# Clock_EasyEDA_Project_File.net
KiCad netlist of a schematic drawn in EasyEDA Pro
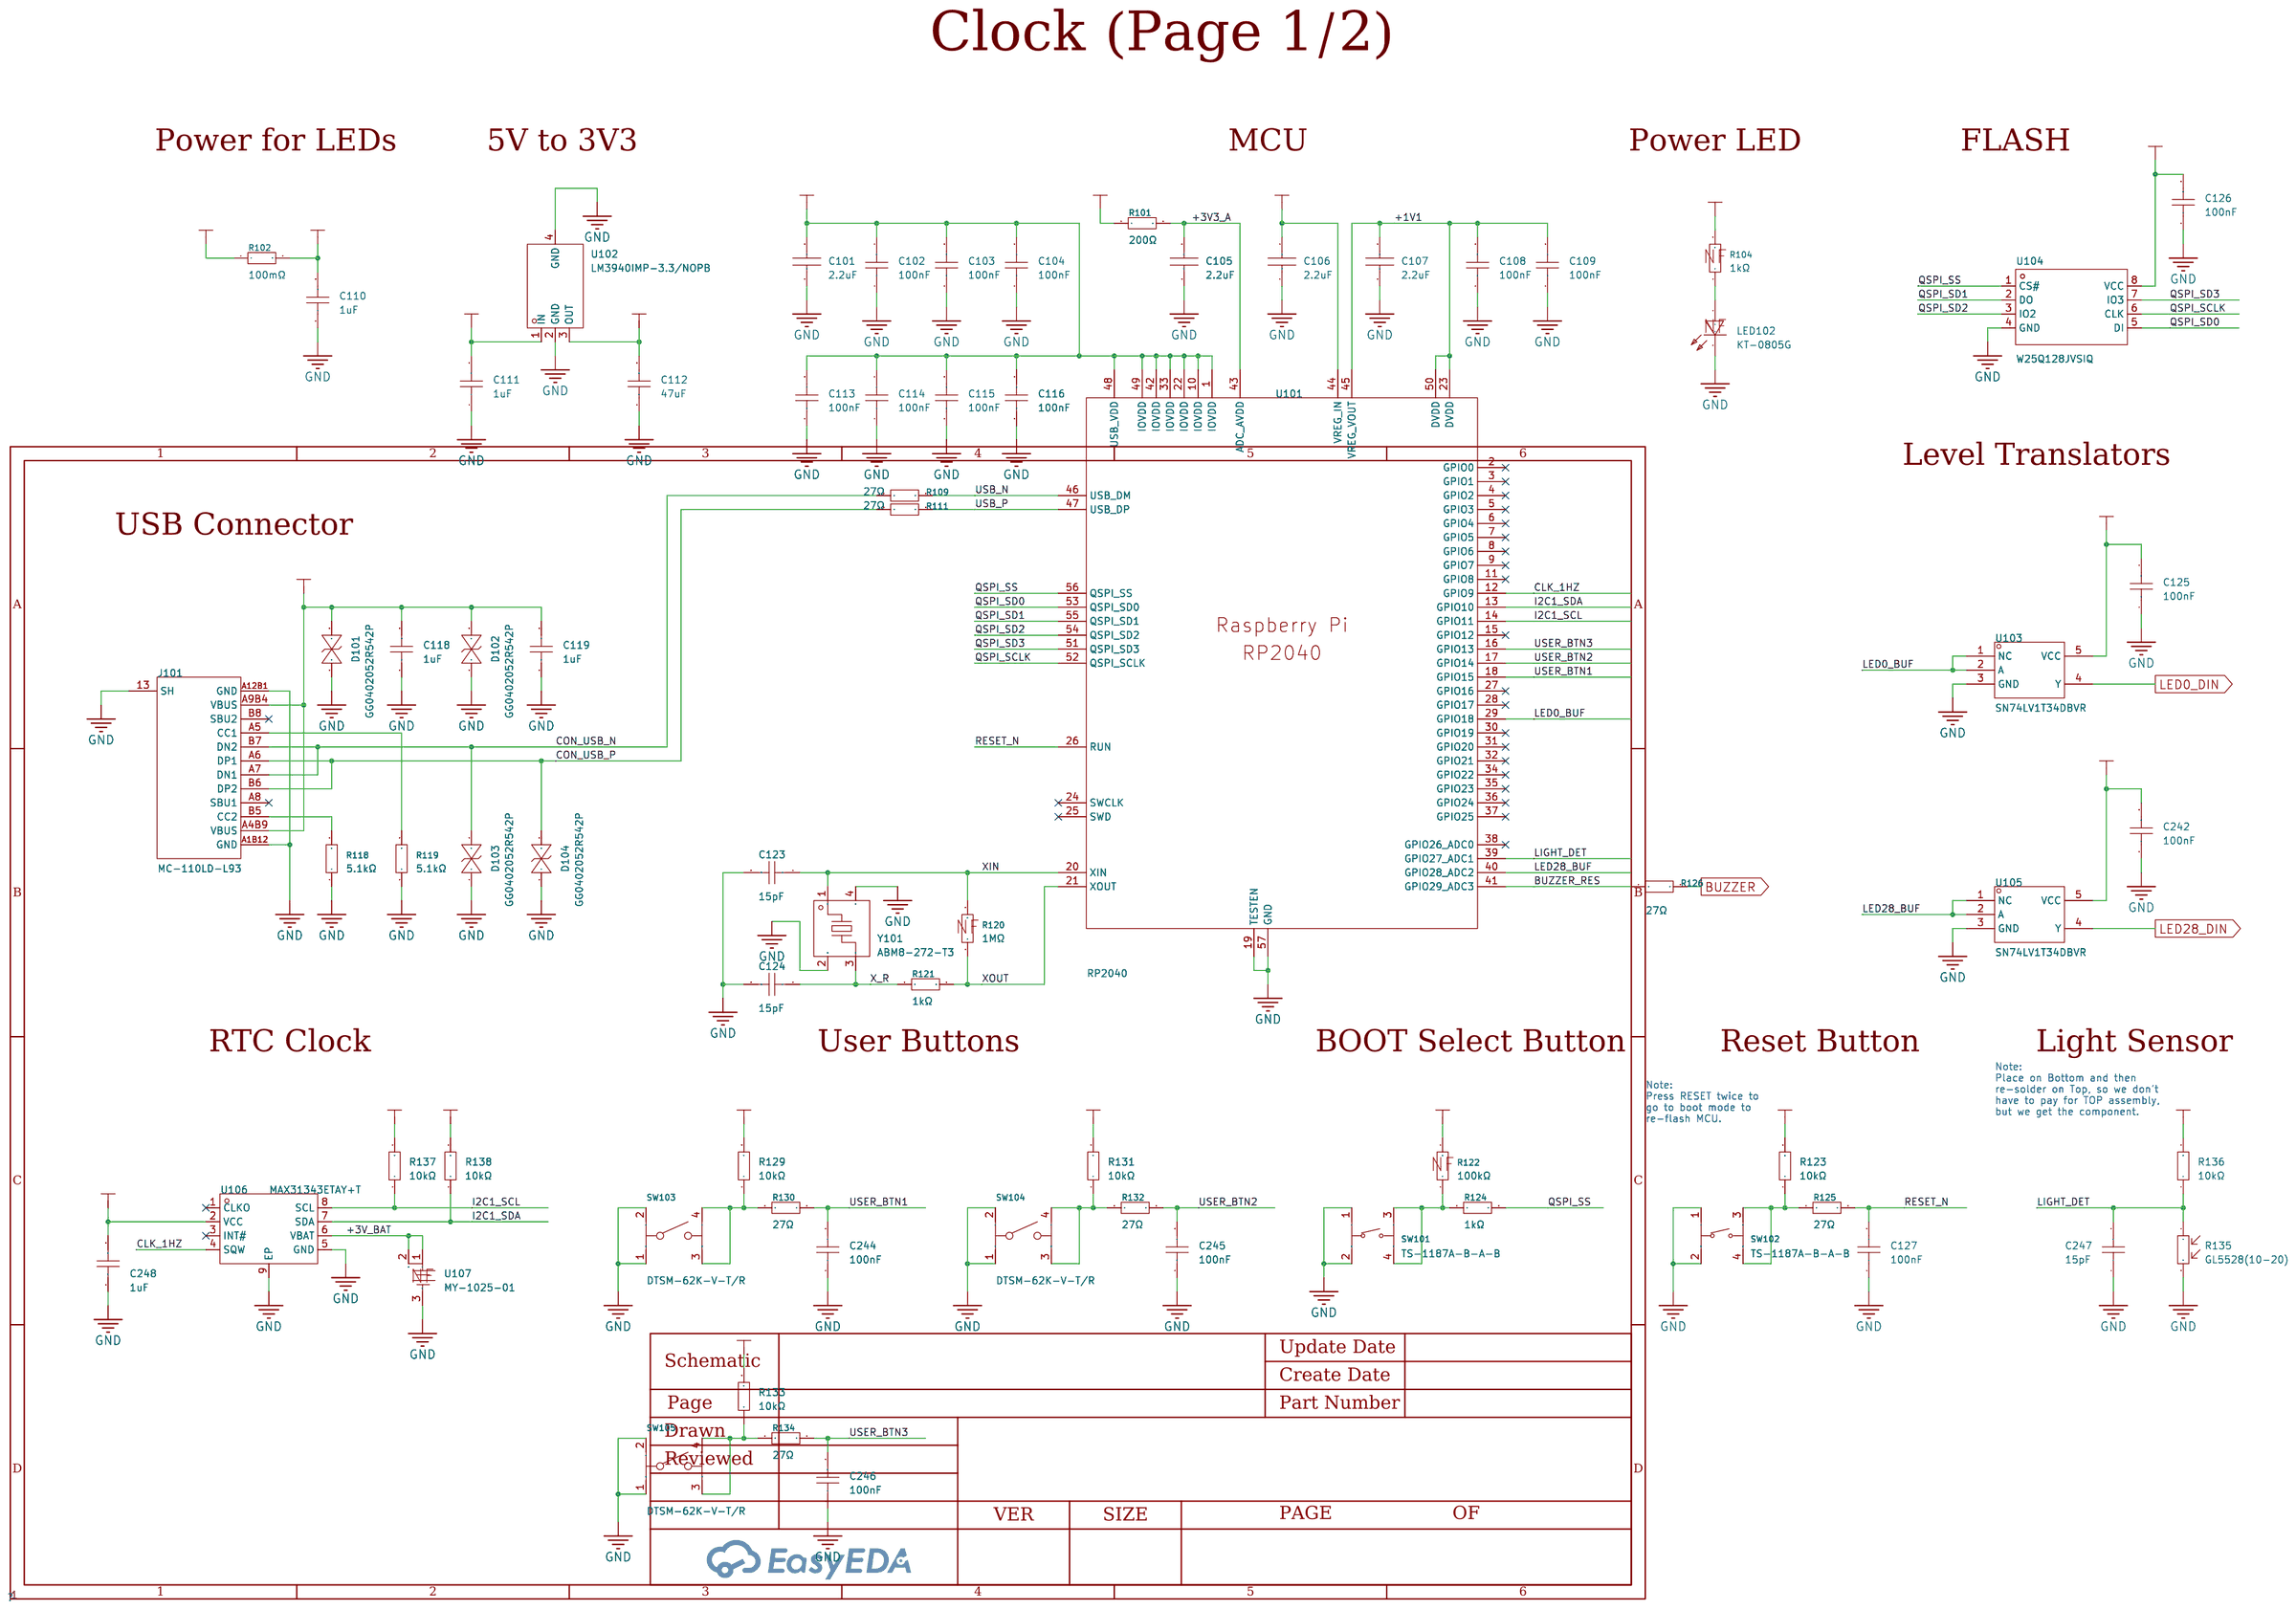
[diagram p0: MCU]
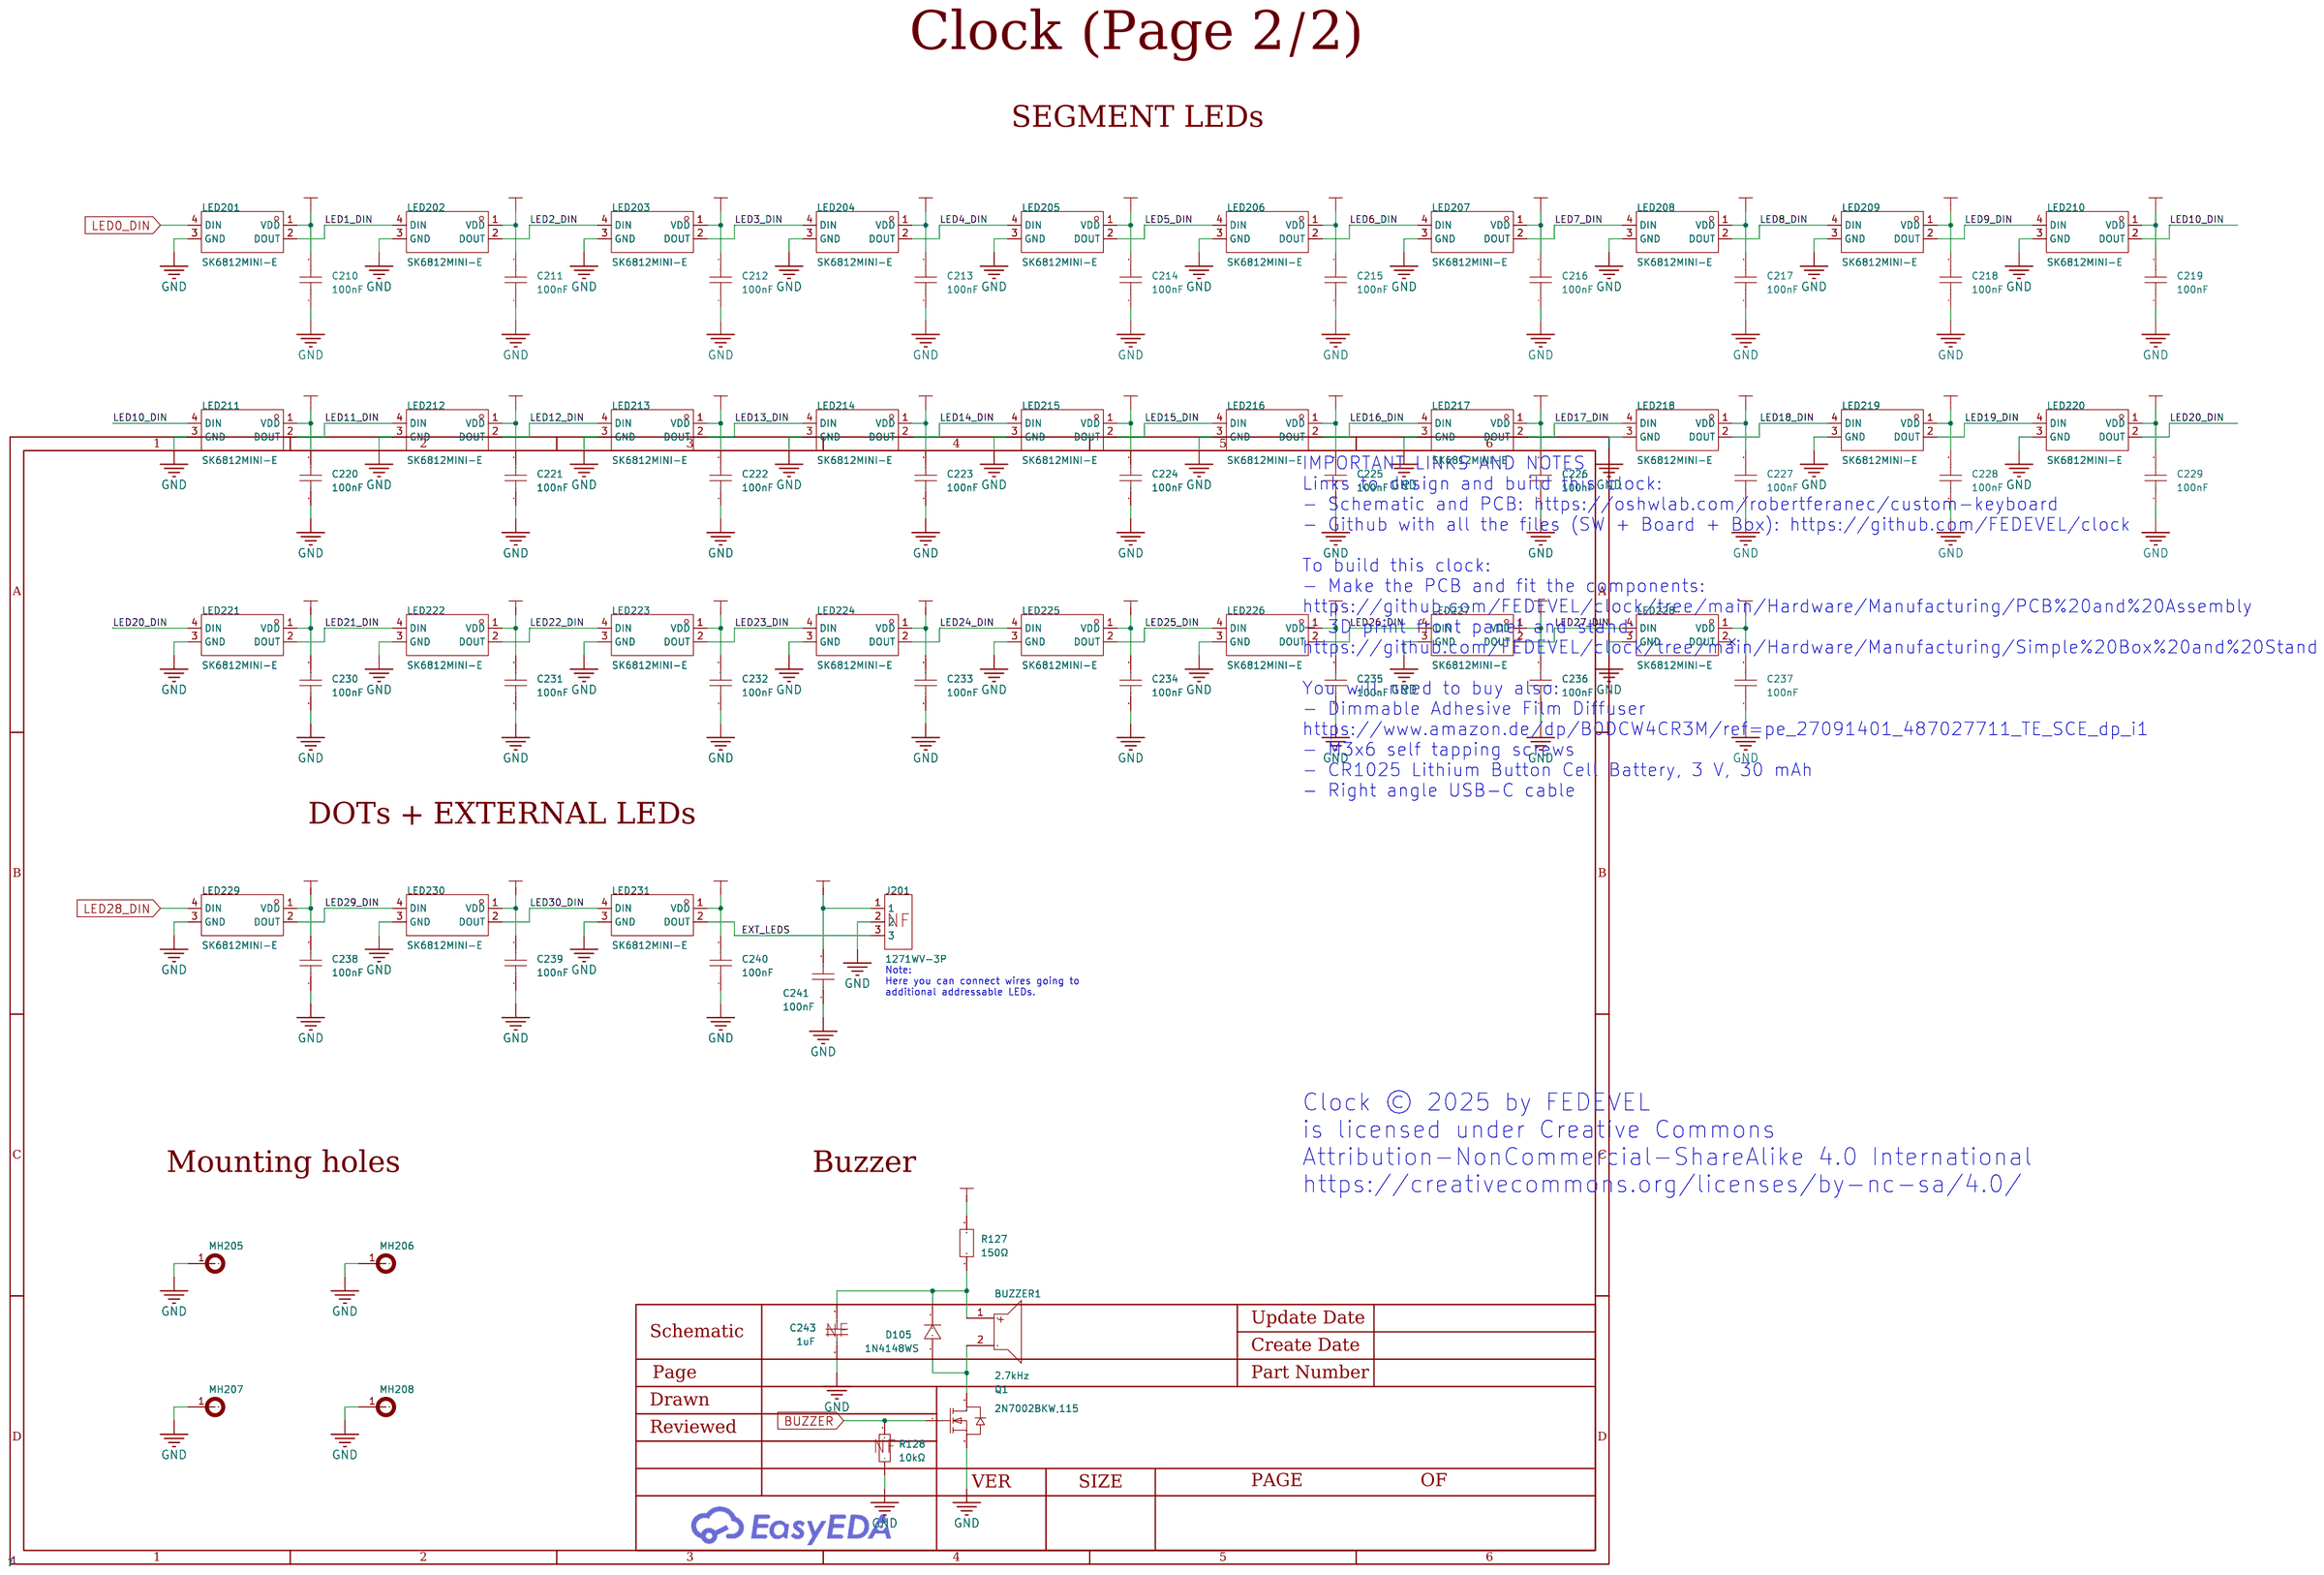
[diagram p1: OTHER]

(export (version "E")
  (design (tool "Eeschema 10.0.6"))
  (components
    (comp (ref "C101")
      (value "2.2uF")
      (footprint "easyedapro:C0402")
      (fields
        (field (name "Manufacturer Part") "CL05A225MQ5NSNC")
        (field (name "Manufacturer") "SAMSUNG(三星)")
      )
      (libsource (lib "easyedapro") (part "CL05A225MQ5NSNC"))
    )
    (comp (ref "C102")
      (value "100nF")
      (footprint "easyedapro:C0402")
      (fields
        (field (name "Manufacturer Part") "CL05B104KO5NNNC")
        (field (name "Manufacturer") "SAMSUNG(三星)")
      )
      (libsource (lib "easyedapro") (part "CL05B104KO5NNNC"))
    )
    (comp (ref "C103")
      (value "100nF")
      (footprint "easyedapro:C0402")
      (fields
        (field (name "Manufacturer Part") "CL05B104KO5NNNC")
        (field (name "Manufacturer") "SAMSUNG(三星)")
      )
      (libsource (lib "easyedapro") (part "CL05B104KO5NNNC"))
    )
    (comp (ref "C104")
      (value "100nF")
      (footprint "easyedapro:C0402")
      (fields
        (field (name "Manufacturer Part") "CL05B104KO5NNNC")
        (field (name "Manufacturer") "SAMSUNG(三星)")
      )
      (libsource (lib "easyedapro") (part "CL05B104KO5NNNC"))
    )
    (comp (ref "C105")
      (value "2.2uF")
      (footprint "easyedapro:C0402")
      (fields
        (field (name "Manufacturer Part") "CL05A225MQ5NSNC")
        (field (name "Manufacturer") "SAMSUNG(三星)")
      )
      (libsource (lib "easyedapro") (part "CL05A225MQ5NSNC"))
    )
    (comp (ref "C106")
      (value "2.2uF")
      (footprint "easyedapro:C0402")
      (fields
        (field (name "Manufacturer Part") "CL05A225MQ5NSNC")
        (field (name "Manufacturer") "SAMSUNG(三星)")
      )
      (libsource (lib "easyedapro") (part "CL05A225MQ5NSNC"))
    )
    (comp (ref "C107")
      (value "2.2uF")
      (footprint "easyedapro:C0402")
      (fields
        (field (name "Manufacturer Part") "CL05A225MQ5NSNC")
        (field (name "Manufacturer") "SAMSUNG(三星)")
      )
      (libsource (lib "easyedapro") (part "CL05A225MQ5NSNC"))
    )
    (comp (ref "C108")
      (value "100nF")
      (footprint "easyedapro:C0402")
      (fields
        (field (name "Manufacturer Part") "CL05B104KO5NNNC")
        (field (name "Manufacturer") "SAMSUNG(三星)")
      )
      (libsource (lib "easyedapro") (part "CL05B104KO5NNNC"))
    )
    (comp (ref "C109")
      (value "100nF")
      (footprint "easyedapro:C0402")
      (fields
        (field (name "Manufacturer Part") "CL05B104KO5NNNC")
        (field (name "Manufacturer") "SAMSUNG(三星)")
      )
      (libsource (lib "easyedapro") (part "CL05B104KO5NNNC"))
    )
    (comp (ref "C110")
      (value "1uF")
      (footprint "easyedapro:C0402")
      (fields
        (field (name "Manufacturer Part") "CL05A105KA5NQNC")
        (field (name "Manufacturer") "SAMSUNG(三星)")
      )
      (libsource (lib "easyedapro") (part "CL05A105KA5NQNC"))
    )
    (comp (ref "C111")
      (value "1uF")
      (footprint "easyedapro:C0402")
      (fields
        (field (name "Manufacturer Part") "CL05A105KA5NQNC")
        (field (name "Manufacturer") "SAMSUNG(三星)")
      )
      (libsource (lib "easyedapro") (part "CL05A105KA5NQNC"))
    )
    (comp (ref "C112")
      (value "47uF")
      (footprint "easyedapro:C1206")
      (fields
        (field (name "Manufacturer Part") "CL31A476MPHNNNE")
        (field (name "Manufacturer") "SAMSUNG(三星)")
      )
      (libsource (lib "easyedapro") (part "CL31A476MPHNNNE"))
    )
    (comp (ref "C113")
      (value "100nF")
      (footprint "easyedapro:C0402")
      (fields
        (field (name "Manufacturer Part") "CL05B104KO5NNNC")
        (field (name "Manufacturer") "SAMSUNG(三星)")
      )
      (libsource (lib "easyedapro") (part "CL05B104KO5NNNC"))
    )
    (comp (ref "C114")
      (value "100nF")
      (footprint "easyedapro:C0402")
      (fields
        (field (name "Manufacturer Part") "CL05B104KO5NNNC")
        (field (name "Manufacturer") "SAMSUNG(三星)")
      )
      (libsource (lib "easyedapro") (part "CL05B104KO5NNNC"))
    )
    (comp (ref "C115")
      (value "100nF")
      (footprint "easyedapro:C0402")
      (fields
        (field (name "Manufacturer Part") "CL05B104KO5NNNC")
        (field (name "Manufacturer") "SAMSUNG(三星)")
      )
      (libsource (lib "easyedapro") (part "CL05B104KO5NNNC"))
    )
    (comp (ref "C116")
      (value "100nF")
      (footprint "easyedapro:C0402")
      (fields
        (field (name "Manufacturer Part") "CL05B104KO5NNNC")
        (field (name "Manufacturer") "SAMSUNG(三星)")
      )
      (libsource (lib "easyedapro") (part "CL05B104KO5NNNC"))
    )
    (comp (ref "C118")
      (value "1uF")
      (footprint "easyedapro:C0402")
      (fields
        (field (name "Manufacturer Part") "CL05A105KA5NQNC")
        (field (name "Manufacturer") "SAMSUNG(三星)")
      )
      (libsource (lib "easyedapro") (part "CL05A105KA5NQNC"))
    )
    (comp (ref "C119")
      (value "1uF")
      (footprint "easyedapro:C0402")
      (fields
        (field (name "Manufacturer Part") "CL05A105KA5NQNC")
        (field (name "Manufacturer") "SAMSUNG(三星)")
      )
      (libsource (lib "easyedapro") (part "CL05A105KA5NQNC"))
    )
    (comp (ref "C123")
      (value "15pF")
      (footprint "easyedapro:C0402")
      (fields
        (field (name "Manufacturer Part") "CL05C150JB5NNNC")
        (field (name "Manufacturer") "SAMSUNG(三星)")
      )
      (libsource (lib "easyedapro") (part "CL05C150JB5NNNC"))
    )
    (comp (ref "C124")
      (value "15pF")
      (footprint "easyedapro:C0402")
      (fields
        (field (name "Manufacturer Part") "CL05C150JB5NNNC")
        (field (name "Manufacturer") "SAMSUNG(三星)")
      )
      (libsource (lib "easyedapro") (part "CL05C150JB5NNNC"))
    )
    (comp (ref "C125")
      (value "100nF")
      (footprint "easyedapro:C0402")
      (fields
        (field (name "Manufacturer Part") "CL05B104KO5NNNC")
        (field (name "Manufacturer") "SAMSUNG(三星)")
      )
      (libsource (lib "easyedapro") (part "CL05B104KO5NNNC"))
    )
    (comp (ref "C126")
      (value "100nF")
      (footprint "easyedapro:C0402")
      (fields
        (field (name "Manufacturer Part") "CL05B104KO5NNNC")
        (field (name "Manufacturer") "SAMSUNG(三星)")
      )
      (libsource (lib "easyedapro") (part "CL05B104KO5NNNC"))
    )
    (comp (ref "C127")
      (value "100nF")
      (footprint "easyedapro:C0402")
      (fields
        (field (name "Manufacturer Part") "CL05B104KO5NNNC")
        (field (name "Manufacturer") "SAMSUNG(三星)")
      )
      (libsource (lib "easyedapro") (part "CL05B104KO5NNNC"))
    )
    (comp (ref "C242")
      (value "100nF")
      (footprint "easyedapro:C0402")
      (fields
        (field (name "Manufacturer Part") "CL05B104KO5NNNC")
        (field (name "Manufacturer") "SAMSUNG(三星)")
      )
      (libsource (lib "easyedapro") (part "CL05B104KO5NNNC"))
    )
    (comp (ref "C244")
      (value "100nF")
      (footprint "easyedapro:C0402")
      (fields
        (field (name "Manufacturer Part") "CL05B104KO5NNNC")
        (field (name "Manufacturer") "SAMSUNG(三星)")
      )
      (libsource (lib "easyedapro") (part "CL05B104KO5NNNC"))
    )
    (comp (ref "C245")
      (value "100nF")
      (footprint "easyedapro:C0402")
      (fields
        (field (name "Manufacturer Part") "CL05B104KO5NNNC")
        (field (name "Manufacturer") "SAMSUNG(三星)")
      )
      (libsource (lib "easyedapro") (part "CL05B104KO5NNNC"))
    )
    (comp (ref "C246")
      (value "100nF")
      (footprint "easyedapro:C0402")
      (fields
        (field (name "Manufacturer Part") "CL05B104KO5NNNC")
        (field (name "Manufacturer") "SAMSUNG(三星)")
      )
      (libsource (lib "easyedapro") (part "CL05B104KO5NNNC"))
    )
    (comp (ref "C247")
      (value "15pF")
      (footprint "easyedapro:C0402")
      (fields
        (field (name "Manufacturer Part") "CL05C150JB5NNNC")
        (field (name "Manufacturer") "SAMSUNG(三星)")
      )
      (libsource (lib "easyedapro") (part "CL05C150JB5NNNC"))
    )
    (comp (ref "C248")
      (value "1uF")
      (footprint "easyedapro:C0402")
      (fields
        (field (name "Manufacturer Part") "CL05A105KA5NQNC")
        (field (name "Manufacturer") "SAMSUNG(三星)")
      )
      (libsource (lib "easyedapro") (part "CL05A105KA5NQNC"))
    )
    (comp (ref "D101")
      (value "GG0402052R542P")
      (footprint "easyedapro:D0402-BI")
      (fields (field (name "Manufacturer") "Kyocera AVX"))
      (libsource (lib "easyedapro") (part "GG0402052R542P"))
    )
    (comp (ref "D102")
      (value "GG0402052R542P")
      (footprint "easyedapro:D0402-BI")
      (fields (field (name "Manufacturer") "Kyocera AVX"))
      (libsource (lib "easyedapro") (part "GG0402052R542P"))
    )
    (comp (ref "D103")
      (value "GG0402052R542P")
      (footprint "easyedapro:D0402-BI")
      (fields (field (name "Manufacturer") "Kyocera AVX"))
      (libsource (lib "easyedapro") (part "GG0402052R542P"))
    )
    (comp (ref "D104")
      (value "GG0402052R542P")
      (footprint "easyedapro:D0402-BI")
      (fields (field (name "Manufacturer") "Kyocera AVX"))
      (libsource (lib "easyedapro") (part "GG0402052R542P"))
    )
    (comp (ref "J101")
      (value "MC-110LD-L93")
      (footprint "easyedapro:USB-C-TH_MC-110LD-L93_1")
      (fields (field (name "Manufacturer") "HANBO(汉博)"))
      (libsource (lib "easyedapro") (part "MC-110LD-L93-RF"))
    )
    (comp (ref "LED102")
      (value "KT-0805G")
      (footprint "easyedapro:LED0805-R-RD")
      (fields (field (name "Manufacturer") "KENTO"))
      (libsource (lib "easyedapro") (part "0805G (Green)"))
    )
    (comp (ref "R101")
      (value "200Ω")
      (footprint "easyedapro:R0402")
      (fields
        (field (name "Manufacturer Part") "0402WGF2000TCE")
        (field (name "Manufacturer") "UNI-ROYAL(厚声)")
      )
      (libsource (lib "easyedapro") (part "0402WGF2000TCE"))
    )
    (comp (ref "R102")
      (value "100mΩ")
      (footprint "easyedapro:R1206")
      (fields
        (field (name "Manufacturer Part") "1206W4F100LT5E")
        (field (name "Manufacturer") "UNI-ROYAL(厚声)")
      )
      (libsource (lib "easyedapro") (part "1206W4F100LT5E"))
    )
    (comp (ref "R104")
      (value "1kΩ")
      (footprint "easyedapro:R0402")
      (fields
        (field (name "Manufacturer Part") "0402WGF1001TCE")
        (field (name "Manufacturer") "UNI-ROYAL(厚声)")
      )
      (libsource (lib "easyedapro") (part "0402WGF1001TCE"))
    )
    (comp (ref "R109")
      (value "27Ω")
      (footprint "easyedapro:R0402")
      (fields
        (field (name "Manufacturer Part") "0402WGF270JTCE")
        (field (name "Manufacturer") "UNI-ROYAL(厚声)")
      )
      (libsource (lib "easyedapro") (part "0402WGF270JTCE"))
    )
    (comp (ref "R111")
      (value "27Ω")
      (footprint "easyedapro:R0402")
      (fields
        (field (name "Manufacturer Part") "0402WGF270JTCE")
        (field (name "Manufacturer") "UNI-ROYAL(厚声)")
      )
      (libsource (lib "easyedapro") (part "0402WGF270JTCE"))
    )
    (comp (ref "R118")
      (value "5.1kΩ")
      (footprint "easyedapro:R0402")
      (fields
        (field (name "Manufacturer Part") "0402WGF5101TCE")
        (field (name "Manufacturer") "UNI-ROYAL(厚声)")
      )
      (libsource (lib "easyedapro") (part "0402WGF5101TCE"))
    )
    (comp (ref "R119")
      (value "5.1kΩ")
      (footprint "easyedapro:R0402")
      (fields
        (field (name "Manufacturer Part") "0402WGF5101TCE")
        (field (name "Manufacturer") "UNI-ROYAL(厚声)")
      )
      (libsource (lib "easyedapro") (part "0402WGF5101TCE"))
    )
    (comp (ref "R120")
      (value "1MΩ")
      (footprint "easyedapro:R0402")
      (fields
        (field (name "Manufacturer Part") "0402WGF1004TCE")
        (field (name "Manufacturer") "UNI-ROYAL(厚声)")
      )
      (libsource (lib "easyedapro") (part "0402WGF1004TCE"))
    )
    (comp (ref "R121")
      (value "1kΩ")
      (footprint "easyedapro:R0402")
      (fields
        (field (name "Manufacturer Part") "0402WGF1001TCE")
        (field (name "Manufacturer") "UNI-ROYAL(厚声)")
      )
      (libsource (lib "easyedapro") (part "0402WGF1001TCE"))
    )
    (comp (ref "R122")
      (value "100kΩ")
      (footprint "easyedapro:R0402")
      (fields
        (field (name "Manufacturer Part") "0402WGF1003TCE")
        (field (name "Manufacturer") "UNI-ROYAL(厚声)")
      )
      (libsource (lib "easyedapro") (part "0402WGF1003TCE"))
    )
    (comp (ref "R123")
      (value "10kΩ")
      (footprint "easyedapro:R0402")
      (fields
        (field (name "Manufacturer Part") "0402WGF1002TCE")
        (field (name "Manufacturer") "UNI-ROYAL(厚声)")
      )
      (libsource (lib "easyedapro") (part "0402WGF1002TCE"))
    )
    (comp (ref "R124")
      (value "1kΩ")
      (footprint "easyedapro:R0402")
      (fields
        (field (name "Manufacturer Part") "0402WGF1001TCE")
        (field (name "Manufacturer") "UNI-ROYAL(厚声)")
      )
      (libsource (lib "easyedapro") (part "0402WGF1001TCE"))
    )
    (comp (ref "R125")
      (value "27Ω")
      (footprint "easyedapro:R0402")
      (fields
        (field (name "Manufacturer Part") "0402WGF270JTCE")
        (field (name "Manufacturer") "UNI-ROYAL(厚声)")
      )
      (libsource (lib "easyedapro") (part "0402WGF270JTCE"))
    )
    (comp (ref "R126")
      (value "27Ω")
      (footprint "easyedapro:R0402")
      (fields
        (field (name "Manufacturer Part") "0402WGF270JTCE")
        (field (name "Manufacturer") "UNI-ROYAL(厚声)")
      )
      (libsource (lib "easyedapro") (part "0402WGF270JTCE"))
    )
    (comp (ref "R129")
      (value "10kΩ")
      (footprint "easyedapro:R0402")
      (fields
        (field (name "Manufacturer Part") "0402WGF1002TCE")
        (field (name "Manufacturer") "UNI-ROYAL(厚声)")
      )
      (libsource (lib "easyedapro") (part "0402WGF1002TCE"))
    )
    (comp (ref "R130")
      (value "27Ω")
      (footprint "easyedapro:R0402")
      (fields
        (field (name "Manufacturer Part") "0402WGF270JTCE")
        (field (name "Manufacturer") "UNI-ROYAL(厚声)")
      )
      (libsource (lib "easyedapro") (part "0402WGF270JTCE"))
    )
    (comp (ref "R131")
      (value "10kΩ")
      (footprint "easyedapro:R0402")
      (fields
        (field (name "Manufacturer Part") "0402WGF1002TCE")
        (field (name "Manufacturer") "UNI-ROYAL(厚声)")
      )
      (libsource (lib "easyedapro") (part "0402WGF1002TCE"))
    )
    (comp (ref "R132")
      (value "27Ω")
      (footprint "easyedapro:R0402")
      (fields
        (field (name "Manufacturer Part") "0402WGF270JTCE")
        (field (name "Manufacturer") "UNI-ROYAL(厚声)")
      )
      (libsource (lib "easyedapro") (part "0402WGF270JTCE"))
    )
    (comp (ref "R133")
      (value "10kΩ")
      (footprint "easyedapro:R0402")
      (fields
        (field (name "Manufacturer Part") "0402WGF1002TCE")
        (field (name "Manufacturer") "UNI-ROYAL(厚声)")
      )
      (libsource (lib "easyedapro") (part "0402WGF1002TCE"))
    )
    (comp (ref "R134")
      (value "27Ω")
      (footprint "easyedapro:R0402")
      (fields
        (field (name "Manufacturer Part") "0402WGF270JTCE")
        (field (name "Manufacturer") "UNI-ROYAL(厚声)")
      )
      (libsource (lib "easyedapro") (part "0402WGF270JTCE"))
    )
    (comp (ref "R135")
      (value "GL5528(10-20)")
      (footprint "easyedapro:RES-TH_L5.1-W4.3-P3.40-D0.5")
      (fields (field (name "Manufacturer") "JCHL(晶创和立)"))
      (libsource (lib "easyedapro") (part "GL5528(10-20)"))
    )
    (comp (ref "R136")
      (value "10kΩ")
      (footprint "easyedapro:R0402")
      (fields
        (field (name "Manufacturer Part") "0402WGF1002TCE")
        (field (name "Manufacturer") "UNI-ROYAL(厚声)")
      )
      (libsource (lib "easyedapro") (part "0402WGF1002TCE"))
    )
    (comp (ref "R137")
      (value "10kΩ")
      (footprint "easyedapro:R0402")
      (fields
        (field (name "Manufacturer Part") "0402WGF1002TCE")
        (field (name "Manufacturer") "UNI-ROYAL(厚声)")
      )
      (libsource (lib "easyedapro") (part "0402WGF1002TCE"))
    )
    (comp (ref "R138")
      (value "10kΩ")
      (footprint "easyedapro:R0402")
      (fields
        (field (name "Manufacturer Part") "0402WGF1002TCE")
        (field (name "Manufacturer") "UNI-ROYAL(厚声)")
      )
      (libsource (lib "easyedapro") (part "0402WGF1002TCE"))
    )
    (comp (ref "SW101")
      (value "TS-1187A-B-A-B")
      (footprint "easyedapro:SW-SMD_4P-L5.1-W5.1-P3.70-LS6.5-TL-2")
      (fields (field (name "Manufacturer") "XKB Connectivity(中国星坤)"))
      (libsource (lib "easyedapro") (part "TS-1187A-B-A-B"))
    )
    (comp (ref "SW102")
      (value "TS-1187A-B-A-B")
      (footprint "easyedapro:SW-SMD_4P-L5.1-W5.1-P3.70-LS6.5-TL-2")
      (fields (field (name "Manufacturer") "XKB Connectivity(中国星坤)"))
      (libsource (lib "easyedapro") (part "TS-1187A-B-A-B"))
    )
    (comp (ref "SW103")
      (value "DTSM-62K-V-T/R")
      (footprint "easyedapro:KEY-SMD_4P-L6.2-W6.2-P4.50-LS9.0")
      (fields (field (name "Manufacturer") "圜达"))
      (libsource (lib "easyedapro") (part "DTSM-62K-V-T/R"))
    )
    (comp (ref "SW104")
      (value "DTSM-62K-V-T/R")
      (footprint "easyedapro:KEY-SMD_4P-L6.2-W6.2-P4.50-LS9.0")
      (fields (field (name "Manufacturer") "圜达"))
      (libsource (lib "easyedapro") (part "DTSM-62K-V-T/R"))
    )
    (comp (ref "SW105")
      (value "DTSM-62K-V-T/R")
      (footprint "easyedapro:KEY-SMD_4P-L6.2-W6.2-P4.50-LS9.0")
      (fields (field (name "Manufacturer") "圜达"))
      (libsource (lib "easyedapro") (part "DTSM-62K-V-T/R"))
    )
    (comp (ref "U101")
      (value "RP2040")
      (footprint "easyedapro:LQFN-56_L7.0-W7.0-P0.4-EP_1")
      (fields (field (name "Manufacturer") "Raspberry Pi(树莓派)"))
      (libsource (lib "easyedapro") (part "RP2040_C2040_RF_v1.0"))
    )
    (comp (ref "U102")
      (value "LM3940IMP-3.3/NOPB")
      (footprint "easyedapro:SOT-223_L6.5-W3.5-P2.30-LS7.0-BR")
      (fields (field (name "Manufacturer") "TI(德州仪器)"))
      (libsource (lib "easyedapro") (part "LM3940IMP-3.3/NOPB"))
    )
    (comp (ref "U103")
      (value "SN74LV1T34DBVR")
      (footprint "easyedapro:SOT-23-5_L2.9-W1.6-P0.95-LS2.8-BR")
      (fields (field (name "Manufacturer") "TI(德州仪器)"))
      (libsource (lib "easyedapro") (part "SN74LV1T34DBVR_RF_v1.0"))
    )
    (comp (ref "U104")
      (value "W25Q128JVSIQ")
      (footprint "easyedapro:SOIC-8_L5.3-W5.3-P1.27-LS8.0-BL")
      (fields (field (name "Manufacturer") "WINBOND(华邦)"))
      (libsource (lib "easyedapro") (part "W25Q128JVSIQTR"))
    )
    (comp (ref "U105")
      (value "SN74LV1T34DBVR")
      (footprint "easyedapro:SOT-23-5_L2.9-W1.6-P0.95-LS2.8-BR")
      (fields (field (name "Manufacturer") "TI(德州仪器)"))
      (libsource (lib "easyedapro") (part "SN74LV1T34DBVR_RF_v1.0"))
    )
    (comp (ref "U106")
      (value "MAX31343ETAY+T")
      (footprint "easyedapro:TDFN-8_L4.0-W3.0-P0.50-BL-EP")
      (fields (field (name "Manufacturer") "ADI(亚德诺)/MAXIM(美信)"))
      (libsource (lib "easyedapro") (part "MAX31343ETAY+T"))
    )
    (comp (ref "U107")
      (value "MY-1025-01")
      (footprint "easyedapro:BAT-SMD_MY-1025-01_1")
      (fields (field (name "Manufacturer") "MYOUNG(美阳)"))
      (libsource (lib "easyedapro") (part "MY-1025-01-RF"))
    )
    (comp (ref "Y101")
      (value "ABM8-272-T3")
      (footprint "easyedapro:CRYSTAL-SMD_4P-L3.2-W2.5-BL")
      (fields (field (name "Manufacturer") "ABRACON"))
      (libsource (lib "easyedapro") (part "ABM8-272-T3_C20625731"))
    )
    (comp (ref "BUZZER1")
      (value "2.7kHz")
      (footprint "easyedapro:BUZ-TH_BD9.0-P4.00-D0.6-FD")
      (fields (field (name "Manufacturer Part") "QMB-09B-03") (field (name "Manufacturer") "华能"))
      (libsource (lib "easyedapro") (part "QMB-09B-03"))
    )
    (comp (ref "C210")
      (value "100nF")
      (footprint "easyedapro:C0402")
      (fields
        (field (name "Manufacturer Part") "CL05B104KO5NNNC")
        (field (name "Manufacturer") "SAMSUNG(三星)")
      )
      (libsource (lib "easyedapro") (part "CL05B104KO5NNNC"))
    )
    (comp (ref "C211")
      (value "100nF")
      (footprint "easyedapro:C0402")
      (fields
        (field (name "Manufacturer Part") "CL05B104KO5NNNC")
        (field (name "Manufacturer") "SAMSUNG(三星)")
      )
      (libsource (lib "easyedapro") (part "CL05B104KO5NNNC"))
    )
    (comp (ref "C212")
      (value "100nF")
      (footprint "easyedapro:C0402")
      (fields
        (field (name "Manufacturer Part") "CL05B104KO5NNNC")
        (field (name "Manufacturer") "SAMSUNG(三星)")
      )
      (libsource (lib "easyedapro") (part "CL05B104KO5NNNC"))
    )
    (comp (ref "C213")
      (value "100nF")
      (footprint "easyedapro:C0402")
      (fields
        (field (name "Manufacturer Part") "CL05B104KO5NNNC")
        (field (name "Manufacturer") "SAMSUNG(三星)")
      )
      (libsource (lib "easyedapro") (part "CL05B104KO5NNNC"))
    )
    (comp (ref "C214")
      (value "100nF")
      (footprint "easyedapro:C0402")
      (fields
        (field (name "Manufacturer Part") "CL05B104KO5NNNC")
        (field (name "Manufacturer") "SAMSUNG(三星)")
      )
      (libsource (lib "easyedapro") (part "CL05B104KO5NNNC"))
    )
    (comp (ref "C215")
      (value "100nF")
      (footprint "easyedapro:C0402")
      (fields
        (field (name "Manufacturer Part") "CL05B104KO5NNNC")
        (field (name "Manufacturer") "SAMSUNG(三星)")
      )
      (libsource (lib "easyedapro") (part "CL05B104KO5NNNC"))
    )
    (comp (ref "C216")
      (value "100nF")
      (footprint "easyedapro:C0402")
      (fields
        (field (name "Manufacturer Part") "CL05B104KO5NNNC")
        (field (name "Manufacturer") "SAMSUNG(三星)")
      )
      (libsource (lib "easyedapro") (part "CL05B104KO5NNNC"))
    )
    (comp (ref "C217")
      (value "100nF")
      (footprint "easyedapro:C0402")
      (fields
        (field (name "Manufacturer Part") "CL05B104KO5NNNC")
        (field (name "Manufacturer") "SAMSUNG(三星)")
      )
      (libsource (lib "easyedapro") (part "CL05B104KO5NNNC"))
    )
    (comp (ref "C218")
      (value "100nF")
      (footprint "easyedapro:C0402")
      (fields
        (field (name "Manufacturer Part") "CL05B104KO5NNNC")
        (field (name "Manufacturer") "SAMSUNG(三星)")
      )
      (libsource (lib "easyedapro") (part "CL05B104KO5NNNC"))
    )
    (comp (ref "C219")
      (value "100nF")
      (footprint "easyedapro:C0402")
      (fields
        (field (name "Manufacturer Part") "CL05B104KO5NNNC")
        (field (name "Manufacturer") "SAMSUNG(三星)")
      )
      (libsource (lib "easyedapro") (part "CL05B104KO5NNNC"))
    )
    (comp (ref "C220")
      (value "100nF")
      (footprint "easyedapro:C0402")
      (fields
        (field (name "Manufacturer Part") "CL05B104KO5NNNC")
        (field (name "Manufacturer") "SAMSUNG(三星)")
      )
      (libsource (lib "easyedapro") (part "CL05B104KO5NNNC"))
    )
    (comp (ref "C221")
      (value "100nF")
      (footprint "easyedapro:C0402")
      (fields
        (field (name "Manufacturer Part") "CL05B104KO5NNNC")
        (field (name "Manufacturer") "SAMSUNG(三星)")
      )
      (libsource (lib "easyedapro") (part "CL05B104KO5NNNC"))
    )
    (comp (ref "C222")
      (value "100nF")
      (footprint "easyedapro:C0402")
      (fields
        (field (name "Manufacturer Part") "CL05B104KO5NNNC")
        (field (name "Manufacturer") "SAMSUNG(三星)")
      )
      (libsource (lib "easyedapro") (part "CL05B104KO5NNNC"))
    )
    (comp (ref "C223")
      (value "100nF")
      (footprint "easyedapro:C0402")
      (fields
        (field (name "Manufacturer Part") "CL05B104KO5NNNC")
        (field (name "Manufacturer") "SAMSUNG(三星)")
      )
      (libsource (lib "easyedapro") (part "CL05B104KO5NNNC"))
    )
    (comp (ref "C224")
      (value "100nF")
      (footprint "easyedapro:C0402")
      (fields
        (field (name "Manufacturer Part") "CL05B104KO5NNNC")
        (field (name "Manufacturer") "SAMSUNG(三星)")
      )
      (libsource (lib "easyedapro") (part "CL05B104KO5NNNC"))
    )
    (comp (ref "C225")
      (value "100nF")
      (footprint "easyedapro:C0402")
      (fields
        (field (name "Manufacturer Part") "CL05B104KO5NNNC")
        (field (name "Manufacturer") "SAMSUNG(三星)")
      )
      (libsource (lib "easyedapro") (part "CL05B104KO5NNNC"))
    )
    (comp (ref "C226")
      (value "100nF")
      (footprint "easyedapro:C0402")
      (fields
        (field (name "Manufacturer Part") "CL05B104KO5NNNC")
        (field (name "Manufacturer") "SAMSUNG(三星)")
      )
      (libsource (lib "easyedapro") (part "CL05B104KO5NNNC"))
    )
    (comp (ref "C227")
      (value "100nF")
      (footprint "easyedapro:C0402")
      (fields
        (field (name "Manufacturer Part") "CL05B104KO5NNNC")
        (field (name "Manufacturer") "SAMSUNG(三星)")
      )
      (libsource (lib "easyedapro") (part "CL05B104KO5NNNC"))
    )
    (comp (ref "C228")
      (value "100nF")
      (footprint "easyedapro:C0402")
      (fields
        (field (name "Manufacturer Part") "CL05B104KO5NNNC")
        (field (name "Manufacturer") "SAMSUNG(三星)")
      )
      (libsource (lib "easyedapro") (part "CL05B104KO5NNNC"))
    )
    (comp (ref "C229")
      (value "100nF")
      (footprint "easyedapro:C0402")
      (fields
        (field (name "Manufacturer Part") "CL05B104KO5NNNC")
        (field (name "Manufacturer") "SAMSUNG(三星)")
      )
      (libsource (lib "easyedapro") (part "CL05B104KO5NNNC"))
    )
    (comp (ref "C230")
      (value "100nF")
      (footprint "easyedapro:C0402")
      (fields
        (field (name "Manufacturer Part") "CL05B104KO5NNNC")
        (field (name "Manufacturer") "SAMSUNG(三星)")
      )
      (libsource (lib "easyedapro") (part "CL05B104KO5NNNC"))
    )
    (comp (ref "C231")
      (value "100nF")
      (footprint "easyedapro:C0402")
      (fields
        (field (name "Manufacturer Part") "CL05B104KO5NNNC")
        (field (name "Manufacturer") "SAMSUNG(三星)")
      )
      (libsource (lib "easyedapro") (part "CL05B104KO5NNNC"))
    )
    (comp (ref "C232")
      (value "100nF")
      (footprint "easyedapro:C0402")
      (fields
        (field (name "Manufacturer Part") "CL05B104KO5NNNC")
        (field (name "Manufacturer") "SAMSUNG(三星)")
      )
      (libsource (lib "easyedapro") (part "CL05B104KO5NNNC"))
    )
    (comp (ref "C233")
      (value "100nF")
      (footprint "easyedapro:C0402")
      (fields
        (field (name "Manufacturer Part") "CL05B104KO5NNNC")
        (field (name "Manufacturer") "SAMSUNG(三星)")
      )
      (libsource (lib "easyedapro") (part "CL05B104KO5NNNC"))
    )
    (comp (ref "C234")
      (value "100nF")
      (footprint "easyedapro:C0402")
      (fields
        (field (name "Manufacturer Part") "CL05B104KO5NNNC")
        (field (name "Manufacturer") "SAMSUNG(三星)")
      )
      (libsource (lib "easyedapro") (part "CL05B104KO5NNNC"))
    )
    (comp (ref "C235")
      (value "100nF")
      (footprint "easyedapro:C0402")
      (fields
        (field (name "Manufacturer Part") "CL05B104KO5NNNC")
        (field (name "Manufacturer") "SAMSUNG(三星)")
      )
      (libsource (lib "easyedapro") (part "CL05B104KO5NNNC"))
    )
    (comp (ref "C236")
      (value "100nF")
      (footprint "easyedapro:C0402")
      (fields
        (field (name "Manufacturer Part") "CL05B104KO5NNNC")
        (field (name "Manufacturer") "SAMSUNG(三星)")
      )
      (libsource (lib "easyedapro") (part "CL05B104KO5NNNC"))
    )
    (comp (ref "C237")
      (value "100nF")
      (footprint "easyedapro:C0402")
      (fields
        (field (name "Manufacturer Part") "CL05B104KO5NNNC")
        (field (name "Manufacturer") "SAMSUNG(三星)")
      )
      (libsource (lib "easyedapro") (part "CL05B104KO5NNNC"))
    )
    (comp (ref "C238")
      (value "100nF")
      (footprint "easyedapro:C0402")
      (fields
        (field (name "Manufacturer Part") "CL05B104KO5NNNC")
        (field (name "Manufacturer") "SAMSUNG(三星)")
      )
      (libsource (lib "easyedapro") (part "CL05B104KO5NNNC"))
    )
    (comp (ref "C239")
      (value "100nF")
      (footprint "easyedapro:C0402")
      (fields
        (field (name "Manufacturer Part") "CL05B104KO5NNNC")
        (field (name "Manufacturer") "SAMSUNG(三星)")
      )
      (libsource (lib "easyedapro") (part "CL05B104KO5NNNC"))
    )
    (comp (ref "C240")
      (value "100nF")
      (footprint "easyedapro:C0402")
      (fields
        (field (name "Manufacturer Part") "CL05B104KO5NNNC")
        (field (name "Manufacturer") "SAMSUNG(三星)")
      )
      (libsource (lib "easyedapro") (part "CL05B104KO5NNNC"))
    )
    (comp (ref "C241")
      (value "100nF")
      (footprint "easyedapro:C0402")
      (fields
        (field (name "Manufacturer Part") "CL05B104KO5NNNC")
        (field (name "Manufacturer") "SAMSUNG(三星)")
      )
      (libsource (lib "easyedapro") (part "CL05B104KO5NNNC"))
    )
    (comp (ref "C243")
      (value "1uF")
      (footprint "easyedapro:C0402")
      (fields
        (field (name "Manufacturer Part") "CL05A105KA5NQNC")
        (field (name "Manufacturer") "SAMSUNG(三星)")
      )
      (libsource (lib "easyedapro") (part "CL05A105KA5NQNC"))
    )
    (comp (ref "D105")
      (value "1N4148WS")
      (footprint "easyedapro:SOD-323_L1.8-W1.3-LS2.5-RD")
      (fields (field (name "Manufacturer") "CJ(江苏长电/长晶)"))
      (libsource (lib "easyedapro") (part "1N4148WS T4"))
    )
    (comp (ref "J201")
      (value "1271WV-3P")
      (footprint "easyedapro:HDR-TH_3P-P1.27-V-M")
      (fields (field (name "Manufacturer") "HanElectricity(瀚源)"))
      (libsource (lib "easyedapro") (part "1271WV-3P"))
    )
    (comp (ref "LED201")
      (value "SK6812MINI-E")
      (footprint "easyedapro:LED-SMD_L3.2-W2.8-TR")
      (fields (field (name "Manufacturer") "欧思科光电"))
      (libsource (lib "easyedapro") (part "SK6812MINI-E_C5149201"))
    )
    (comp (ref "LED202")
      (value "SK6812MINI-E")
      (footprint "easyedapro:LED-SMD_L3.2-W2.8-TR")
      (fields (field (name "Manufacturer") "欧思科光电"))
      (libsource (lib "easyedapro") (part "SK6812MINI-E_C5149201"))
    )
    (comp (ref "LED203")
      (value "SK6812MINI-E")
      (footprint "easyedapro:LED-SMD_L3.2-W2.8-TR")
      (fields (field (name "Manufacturer") "欧思科光电"))
      (libsource (lib "easyedapro") (part "SK6812MINI-E_C5149201"))
    )
    (comp (ref "LED204")
      (value "SK6812MINI-E")
      (footprint "easyedapro:LED-SMD_L3.2-W2.8-TR")
      (fields (field (name "Manufacturer") "欧思科光电"))
      (libsource (lib "easyedapro") (part "SK6812MINI-E_C5149201"))
    )
    (comp (ref "LED205")
      (value "SK6812MINI-E")
      (footprint "easyedapro:LED-SMD_L3.2-W2.8-TR")
      (fields (field (name "Manufacturer") "欧思科光电"))
      (libsource (lib "easyedapro") (part "SK6812MINI-E_C5149201"))
    )
    (comp (ref "LED206")
      (value "SK6812MINI-E")
      (footprint "easyedapro:LED-SMD_L3.2-W2.8-TR")
      (fields (field (name "Manufacturer") "欧思科光电"))
      (libsource (lib "easyedapro") (part "SK6812MINI-E_C5149201"))
    )
    (comp (ref "LED207")
      (value "SK6812MINI-E")
      (footprint "easyedapro:LED-SMD_L3.2-W2.8-TR")
      (fields (field (name "Manufacturer") "欧思科光电"))
      (libsource (lib "easyedapro") (part "SK6812MINI-E_C5149201"))
    )
    (comp (ref "LED208")
      (value "SK6812MINI-E")
      (footprint "easyedapro:LED-SMD_L3.2-W2.8-TR")
      (fields (field (name "Manufacturer") "欧思科光电"))
      (libsource (lib "easyedapro") (part "SK6812MINI-E_C5149201"))
    )
    (comp (ref "LED209")
      (value "SK6812MINI-E")
      (footprint "easyedapro:LED-SMD_L3.2-W2.8-TR")
      (fields (field (name "Manufacturer") "欧思科光电"))
      (libsource (lib "easyedapro") (part "SK6812MINI-E_C5149201"))
    )
    (comp (ref "LED210")
      (value "SK6812MINI-E")
      (footprint "easyedapro:LED-SMD_L3.2-W2.8-TR")
      (fields (field (name "Manufacturer") "欧思科光电"))
      (libsource (lib "easyedapro") (part "SK6812MINI-E_C5149201"))
    )
    (comp (ref "LED211")
      (value "SK6812MINI-E")
      (footprint "easyedapro:LED-SMD_L3.2-W2.8-TR")
      (fields (field (name "Manufacturer") "欧思科光电"))
      (libsource (lib "easyedapro") (part "SK6812MINI-E_C5149201"))
    )
    (comp (ref "LED212")
      (value "SK6812MINI-E")
      (footprint "easyedapro:LED-SMD_L3.2-W2.8-TR")
      (fields (field (name "Manufacturer") "欧思科光电"))
      (libsource (lib "easyedapro") (part "SK6812MINI-E_C5149201"))
    )
    (comp (ref "LED213")
      (value "SK6812MINI-E")
      (footprint "easyedapro:LED-SMD_L3.2-W2.8-TR")
      (fields (field (name "Manufacturer") "欧思科光电"))
      (libsource (lib "easyedapro") (part "SK6812MINI-E_C5149201"))
    )
    (comp (ref "LED214")
      (value "SK6812MINI-E")
      (footprint "easyedapro:LED-SMD_L3.2-W2.8-TR")
      (fields (field (name "Manufacturer") "欧思科光电"))
      (libsource (lib "easyedapro") (part "SK6812MINI-E_C5149201"))
    )
    (comp (ref "LED215")
      (value "SK6812MINI-E")
      (footprint "easyedapro:LED-SMD_L3.2-W2.8-TR")
      (fields (field (name "Manufacturer") "欧思科光电"))
      (libsource (lib "easyedapro") (part "SK6812MINI-E_C5149201"))
    )
    (comp (ref "LED216")
      (value "SK6812MINI-E")
      (footprint "easyedapro:LED-SMD_L3.2-W2.8-TR")
      (fields (field (name "Manufacturer") "欧思科光电"))
      (libsource (lib "easyedapro") (part "SK6812MINI-E_C5149201"))
    )
    (comp (ref "LED217")
      (value "SK6812MINI-E")
      (footprint "easyedapro:LED-SMD_L3.2-W2.8-TR")
      (fields (field (name "Manufacturer") "欧思科光电"))
      (libsource (lib "easyedapro") (part "SK6812MINI-E_C5149201"))
    )
    (comp (ref "LED218")
      (value "SK6812MINI-E")
      (footprint "easyedapro:LED-SMD_L3.2-W2.8-TR")
      (fields (field (name "Manufacturer") "欧思科光电"))
      (libsource (lib "easyedapro") (part "SK6812MINI-E_C5149201"))
    )
    (comp (ref "LED219")
      (value "SK6812MINI-E")
      (footprint "easyedapro:LED-SMD_L3.2-W2.8-TR")
      (fields (field (name "Manufacturer") "欧思科光电"))
      (libsource (lib "easyedapro") (part "SK6812MINI-E_C5149201"))
    )
    (comp (ref "LED220")
      (value "SK6812MINI-E")
      (footprint "easyedapro:LED-SMD_L3.2-W2.8-TR")
      (fields (field (name "Manufacturer") "欧思科光电"))
      (libsource (lib "easyedapro") (part "SK6812MINI-E_C5149201"))
    )
    (comp (ref "LED221")
      (value "SK6812MINI-E")
      (footprint "easyedapro:LED-SMD_L3.2-W2.8-TR")
      (fields (field (name "Manufacturer") "欧思科光电"))
      (libsource (lib "easyedapro") (part "SK6812MINI-E_C5149201"))
    )
    (comp (ref "LED222")
      (value "SK6812MINI-E")
      (footprint "easyedapro:LED-SMD_L3.2-W2.8-TR")
      (fields (field (name "Manufacturer") "欧思科光电"))
      (libsource (lib "easyedapro") (part "SK6812MINI-E_C5149201"))
    )
    (comp (ref "LED223")
      (value "SK6812MINI-E")
      (footprint "easyedapro:LED-SMD_L3.2-W2.8-TR")
      (fields (field (name "Manufacturer") "欧思科光电"))
      (libsource (lib "easyedapro") (part "SK6812MINI-E_C5149201"))
    )
    (comp (ref "LED224")
      (value "SK6812MINI-E")
      (footprint "easyedapro:LED-SMD_L3.2-W2.8-TR")
      (fields (field (name "Manufacturer") "欧思科光电"))
      (libsource (lib "easyedapro") (part "SK6812MINI-E_C5149201"))
    )
    (comp (ref "LED225")
      (value "SK6812MINI-E")
      (footprint "easyedapro:LED-SMD_L3.2-W2.8-TR")
      (fields (field (name "Manufacturer") "欧思科光电"))
      (libsource (lib "easyedapro") (part "SK6812MINI-E_C5149201"))
    )
    (comp (ref "LED226")
      (value "SK6812MINI-E")
      (footprint "easyedapro:LED-SMD_L3.2-W2.8-TR")
      (fields (field (name "Manufacturer") "欧思科光电"))
      (libsource (lib "easyedapro") (part "SK6812MINI-E_C5149201"))
    )
    (comp (ref "LED227")
      (value "SK6812MINI-E")
      (footprint "easyedapro:LED-SMD_L3.2-W2.8-TR")
      (fields (field (name "Manufacturer") "欧思科光电"))
      (libsource (lib "easyedapro") (part "SK6812MINI-E_C5149201"))
    )
    (comp (ref "LED228")
      (value "SK6812MINI-E")
      (footprint "easyedapro:LED-SMD_L3.2-W2.8-TR")
      (fields (field (name "Manufacturer") "欧思科光电"))
      (libsource (lib "easyedapro") (part "SK6812MINI-E_C5149201"))
    )
    (comp (ref "LED229")
      (value "SK6812MINI-E")
      (footprint "easyedapro:LED-SMD_L3.2-W2.8-TR")
      (fields (field (name "Manufacturer") "欧思科光电"))
      (libsource (lib "easyedapro") (part "SK6812MINI-E_C5149201"))
    )
    (comp (ref "LED230")
      (value "SK6812MINI-E")
      (footprint "easyedapro:LED-SMD_L3.2-W2.8-TR")
      (fields (field (name "Manufacturer") "欧思科光电"))
      (libsource (lib "easyedapro") (part "SK6812MINI-E_C5149201"))
    )
    (comp (ref "LED231")
      (value "SK6812MINI-E")
      (footprint "easyedapro:LED-SMD_L3.2-W2.8-TR")
      (fields (field (name "Manufacturer") "欧思科光电"))
      (libsource (lib "easyedapro") (part "SK6812MINI-E_C5149201"))
    )
    (comp (ref "MH205")
      (value "~")
      (footprint "easyedapro:MH_7.5X3.2MM_RF_v1.0")
      (libsource (lib "easyedapro") (part "MH_7.5X3.2MM_RF_v1.0"))
    )
    (comp (ref "MH206")
      (value "~")
      (footprint "easyedapro:MH_7.5X3.2MM_RF_v1.0")
      (libsource (lib "easyedapro") (part "MH_7.5X3.2MM_RF_v1.0"))
    )
    (comp (ref "MH207")
      (value "~")
      (footprint "easyedapro:MH_7.5X3.2MM_RF_v1.0")
      (libsource (lib "easyedapro") (part "MH_7.5X3.2MM_RF_v1.0"))
    )
    (comp (ref "MH208")
      (value "~")
      (footprint "easyedapro:MH_7.5X3.2MM_RF_v1.0")
      (libsource (lib "easyedapro") (part "MH_7.5X3.2MM_RF_v1.0"))
    )
    (comp (ref "Q1")
      (value "2N7002BKW,115")
      (footprint "easyedapro:SOT-323_L2.0-W1.3-P1.30-LS2.1-BR")
      (fields (field (name "Manufacturer") "Nexperia(安世)"))
      (libsource (lib "easyedapro") (part "2N7002BKW,115"))
    )
    (comp (ref "R127")
      (value "150Ω")
      (footprint "easyedapro:R1206")
      (fields
        (field (name "Manufacturer Part") "AS0606J0151T5E")
        (field (name "Manufacturer") "UNI-ROYAL(厚声)")
      )
      (libsource (lib "easyedapro") (part "AS06W2J0151T5E"))
    )
    (comp (ref "R128")
      (value "10kΩ")
      (footprint "easyedapro:R0402")
      (fields
        (field (name "Manufacturer Part") "0402WGF1002TCE")
        (field (name "Manufacturer") "UNI-ROYAL(厚声)")
      )
      (libsource (lib "easyedapro") (part "0402WGF1002TCE"))
    )
  )
  (nets
    (net (code "1") (name "+1V1") (class "Default")
      (node (ref "C107") (pin "2") (pinfunction "2_2") (pintype "unspecified"))
      (node (ref "C108") (pin "2") (pinfunction "2_2") (pintype "unspecified"))
      (node (ref "C109") (pin "2") (pinfunction "2_2") (pintype "unspecified"))
      (node (ref "U101") (pin "23") (pinfunction "DVDD_23") (pintype "bidirectional"))
      (node (ref "U101") (pin "45") (pinfunction "VREG_VOUT_45") (pintype "bidirectional"))
      (node (ref "U101") (pin "50") (pinfunction "DVDD_50") (pintype "bidirectional"))
    )
    (net (code "2") (name "+3V3") (class "Default")
      (node (ref "C101") (pin "2") (pinfunction "2_2") (pintype "unspecified"))
      (node (ref "C102") (pin "2") (pinfunction "2_2") (pintype "unspecified"))
      (node (ref "C103") (pin "2") (pinfunction "2_2") (pintype "unspecified"))
      (node (ref "C104") (pin "2") (pinfunction "2_2") (pintype "unspecified"))
      (node (ref "C106") (pin "2") (pinfunction "2_2") (pintype "unspecified"))
      (node (ref "C112") (pin "2") (pinfunction "2_2") (pintype "unspecified"))
      (node (ref "C113") (pin "2") (pinfunction "2_2") (pintype "unspecified"))
      (node (ref "C114") (pin "2") (pinfunction "2_2") (pintype "unspecified"))
      (node (ref "C115") (pin "2") (pinfunction "2_2") (pintype "unspecified"))
      (node (ref "C116") (pin "2") (pinfunction "2_2") (pintype "unspecified"))
      (node (ref "C126") (pin "2") (pinfunction "2_2") (pintype "unspecified"))
      (node (ref "C248") (pin "2") (pinfunction "2_2") (pintype "unspecified"))
      (node (ref "R101") (pin "1") (pinfunction "1_1") (pintype "input"))
      (node (ref "R104") (pin "2") (pinfunction "2_2") (pintype "input"))
      (node (ref "R122") (pin "2") (pinfunction "2_2") (pintype "input"))
      (node (ref "R123") (pin "2") (pinfunction "2_2") (pintype "input"))
      (node (ref "R129") (pin "2") (pinfunction "2_2") (pintype "input"))
      (node (ref "R131") (pin "2") (pinfunction "2_2") (pintype "input"))
      (node (ref "R133") (pin "2") (pinfunction "2_2") (pintype "input"))
      (node (ref "R136") (pin "2") (pinfunction "2_2") (pintype "input"))
      (node (ref "R137") (pin "2") (pinfunction "2_2") (pintype "input"))
      (node (ref "R138") (pin "2") (pinfunction "2_2") (pintype "input"))
      (node (ref "U101") (pin "1") (pinfunction "IOVDD_1") (pintype "bidirectional"))
      (node (ref "U101") (pin "10") (pinfunction "IOVDD_10") (pintype "bidirectional"))
      (node (ref "U101") (pin "22") (pinfunction "IOVDD_22") (pintype "bidirectional"))
      (node (ref "U101") (pin "33") (pinfunction "IOVDD_33") (pintype "bidirectional"))
      (node (ref "U101") (pin "42") (pinfunction "IOVDD_42") (pintype "bidirectional"))
      (node (ref "U101") (pin "44") (pinfunction "VREG_IN_44") (pintype "bidirectional"))
      (node (ref "U101") (pin "48") (pinfunction "USB_VDD_48") (pintype "bidirectional"))
      (node (ref "U101") (pin "49") (pinfunction "IOVDD_49") (pintype "bidirectional"))
      (node (ref "U102") (pin "3") (pinfunction "OUT_3") (pintype "unspecified"))
      (node (ref "U104") (pin "8") (pinfunction "VCC_8") (pintype "unspecified"))
      (node (ref "U106") (pin "2") (pinfunction "VCC_2") (pintype "unspecified"))
    )
    (net (code "3") (name "+3V3_A") (class "Default")
      (node (ref "C105") (pin "2") (pinfunction "2_2") (pintype "unspecified"))
      (node (ref "R101") (pin "2") (pinfunction "2_2") (pintype "input"))
      (node (ref "U101") (pin "43") (pinfunction "ADC_AVDD_43") (pintype "bidirectional"))
    )
    (net (code "4") (name "+3V_BAT") (class "Default")
      (node (ref "U106") (pin "6") (pinfunction "VBAT_6") (pintype "unspecified"))
      (node (ref "U107") (pin "1") (pinfunction "1_1") (pintype "input"))
      (node (ref "U107") (pin "2") (pinfunction "2_2") (pintype "input"))
    )
    (net (code "5") (name "+5V_LEDS") (class "Default")
      (node (ref "C110") (pin "2") (pinfunction "2_2") (pintype "unspecified"))
      (node (ref "C210") (pin "2") (pinfunction "2_2") (pintype "unspecified"))
      (node (ref "C211") (pin "2") (pinfunction "2_2") (pintype "unspecified"))
      (node (ref "C212") (pin "2") (pinfunction "2_2") (pintype "unspecified"))
      (node (ref "C213") (pin "2") (pinfunction "2_2") (pintype "unspecified"))
      (node (ref "C214") (pin "2") (pinfunction "2_2") (pintype "unspecified"))
      (node (ref "C215") (pin "2") (pinfunction "2_2") (pintype "unspecified"))
      (node (ref "C216") (pin "2") (pinfunction "2_2") (pintype "unspecified"))
      (node (ref "C217") (pin "2") (pinfunction "2_2") (pintype "unspecified"))
      (node (ref "C218") (pin "2") (pinfunction "2_2") (pintype "unspecified"))
      (node (ref "C219") (pin "2") (pinfunction "2_2") (pintype "unspecified"))
      (node (ref "C220") (pin "2") (pinfunction "2_2") (pintype "unspecified"))
      (node (ref "C221") (pin "2") (pinfunction "2_2") (pintype "unspecified"))
      (node (ref "C222") (pin "2") (pinfunction "2_2") (pintype "unspecified"))
      (node (ref "C223") (pin "2") (pinfunction "2_2") (pintype "unspecified"))
      (node (ref "C224") (pin "2") (pinfunction "2_2") (pintype "unspecified"))
      (node (ref "C225") (pin "2") (pinfunction "2_2") (pintype "unspecified"))
      (node (ref "C226") (pin "2") (pinfunction "2_2") (pintype "unspecified"))
      (node (ref "C227") (pin "2") (pinfunction "2_2") (pintype "unspecified"))
      (node (ref "C228") (pin "2") (pinfunction "2_2") (pintype "unspecified"))
      (node (ref "C229") (pin "2") (pinfunction "2_2") (pintype "unspecified"))
      (node (ref "C230") (pin "2") (pinfunction "2_2") (pintype "unspecified"))
      (node (ref "C231") (pin "2") (pinfunction "2_2") (pintype "unspecified"))
      (node (ref "C232") (pin "2") (pinfunction "2_2") (pintype "unspecified"))
      (node (ref "C233") (pin "2") (pinfunction "2_2") (pintype "unspecified"))
      (node (ref "C234") (pin "2") (pinfunction "2_2") (pintype "unspecified"))
      (node (ref "C235") (pin "2") (pinfunction "2_2") (pintype "unspecified"))
      (node (ref "C236") (pin "2") (pinfunction "2_2") (pintype "unspecified"))
      (node (ref "C237") (pin "2") (pinfunction "2_2") (pintype "unspecified"))
      (node (ref "C238") (pin "2") (pinfunction "2_2") (pintype "unspecified"))
      (node (ref "C239") (pin "2") (pinfunction "2_2") (pintype "unspecified"))
      (node (ref "C240") (pin "2") (pinfunction "2_2") (pintype "unspecified"))
      (node (ref "C241") (pin "2") (pinfunction "2_2") (pintype "unspecified"))
      (node (ref "J201") (pin "1") (pinfunction "1_1") (pintype "unspecified"))
      (node (ref "LED201") (pin "1") (pinfunction "VDD_1") (pintype "unspecified"))
      (node (ref "LED202") (pin "1") (pinfunction "VDD_1") (pintype "unspecified"))
      (node (ref "LED203") (pin "1") (pinfunction "VDD_1") (pintype "unspecified"))
      (node (ref "LED204") (pin "1") (pinfunction "VDD_1") (pintype "unspecified"))
      (node (ref "LED205") (pin "1") (pinfunction "VDD_1") (pintype "unspecified"))
      (node (ref "LED206") (pin "1") (pinfunction "VDD_1") (pintype "unspecified"))
      (node (ref "LED207") (pin "1") (pinfunction "VDD_1") (pintype "unspecified"))
      (node (ref "LED208") (pin "1") (pinfunction "VDD_1") (pintype "unspecified"))
      (node (ref "LED209") (pin "1") (pinfunction "VDD_1") (pintype "unspecified"))
      (node (ref "LED210") (pin "1") (pinfunction "VDD_1") (pintype "unspecified"))
      (node (ref "LED211") (pin "1") (pinfunction "VDD_1") (pintype "unspecified"))
      (node (ref "LED212") (pin "1") (pinfunction "VDD_1") (pintype "unspecified"))
      (node (ref "LED213") (pin "1") (pinfunction "VDD_1") (pintype "unspecified"))
      (node (ref "LED214") (pin "1") (pinfunction "VDD_1") (pintype "unspecified"))
      (node (ref "LED215") (pin "1") (pinfunction "VDD_1") (pintype "unspecified"))
      (node (ref "LED216") (pin "1") (pinfunction "VDD_1") (pintype "unspecified"))
      (node (ref "LED217") (pin "1") (pinfunction "VDD_1") (pintype "unspecified"))
      (node (ref "LED218") (pin "1") (pinfunction "VDD_1") (pintype "unspecified"))
      (node (ref "LED219") (pin "1") (pinfunction "VDD_1") (pintype "unspecified"))
      (node (ref "LED220") (pin "1") (pinfunction "VDD_1") (pintype "unspecified"))
      (node (ref "LED221") (pin "1") (pinfunction "VDD_1") (pintype "unspecified"))
      (node (ref "LED222") (pin "1") (pinfunction "VDD_1") (pintype "unspecified"))
      (node (ref "LED223") (pin "1") (pinfunction "VDD_1") (pintype "unspecified"))
      (node (ref "LED224") (pin "1") (pinfunction "VDD_1") (pintype "unspecified"))
      (node (ref "LED225") (pin "1") (pinfunction "VDD_1") (pintype "unspecified"))
      (node (ref "LED226") (pin "1") (pinfunction "VDD_1") (pintype "unspecified"))
      (node (ref "LED227") (pin "1") (pinfunction "VDD_1") (pintype "unspecified"))
      (node (ref "LED228") (pin "1") (pinfunction "VDD_1") (pintype "unspecified"))
      (node (ref "LED229") (pin "1") (pinfunction "VDD_1") (pintype "unspecified"))
      (node (ref "LED230") (pin "1") (pinfunction "VDD_1") (pintype "unspecified"))
      (node (ref "LED231") (pin "1") (pinfunction "VDD_1") (pintype "unspecified"))
      (node (ref "R102") (pin "2") (pinfunction "2_2") (pintype "input"))
    )
    (net (code "6") (name "+5V_USB") (class "Default")
      (node (ref "C111") (pin "2") (pinfunction "2_2") (pintype "unspecified"))
      (node (ref "C118") (pin "2") (pinfunction "2_2") (pintype "unspecified"))
      (node (ref "C119") (pin "2") (pinfunction "2_2") (pintype "unspecified"))
      (node (ref "C125") (pin "2") (pinfunction "2_2") (pintype "unspecified"))
      (node (ref "C242") (pin "2") (pinfunction "2_2") (pintype "unspecified"))
      (node (ref "D101") (pin "2") (pinfunction "2_2") (pintype "input"))
      (node (ref "D102") (pin "2") (pinfunction "2_2") (pintype "input"))
      (node (ref "J101") (pin "A4B9") (pinfunction "VBUS_A4B9") (pintype "unspecified"))
      (node (ref "J101") (pin "A9B4") (pinfunction "VBUS_A9B4") (pintype "unspecified"))
      (node (ref "R102") (pin "1") (pinfunction "1_1") (pintype "input"))
      (node (ref "R127") (pin "2") (pinfunction "2_2") (pintype "unspecified"))
      (node (ref "U102") (pin "1") (pinfunction "IN_1") (pintype "unspecified"))
      (node (ref "U103") (pin "5") (pinfunction "VCC_5") (pintype "unspecified"))
      (node (ref "U105") (pin "5") (pinfunction "VCC_5") (pintype "unspecified"))
    )
    (net (code "7") (name "BUZZER") (class "Default")
      (node (ref "Q1") (pin "1") (pinfunction "G_1") (pintype "unspecified"))
      (node (ref "R126") (pin "2") (pinfunction "2_2") (pintype "input"))
      (node (ref "R128") (pin "2") (pinfunction "2_2") (pintype "input"))
    )
    (net (code "8") (name "BUZZER_RES") (class "Default")
      (node (ref "R126") (pin "1") (pinfunction "1_1") (pintype "input"))
      (node (ref "U101") (pin "41") (pinfunction "GPIO29_ADC3_41") (pintype "bidirectional"))
    )
    (net (code "9") (name "CLK_1HZ") (class "Default")
      (node (ref "U101") (pin "12") (pinfunction "GPIO9_12") (pintype "bidirectional"))
      (node (ref "U106") (pin "4") (pinfunction "SQW_4") (pintype "unspecified"))
    )
    (net (code "10") (name "CON_USB_N") (class "Default")
      (node (ref "D103") (pin "2") (pinfunction "2_2") (pintype "input"))
      (node (ref "J101") (pin "A7") (pinfunction "DN1_A7") (pintype "unspecified"))
      (node (ref "J101") (pin "B7") (pinfunction "DN2_B7") (pintype "unspecified"))
      (node (ref "R109") (pin "1") (pinfunction "1_1") (pintype "input"))
    )
    (net (code "11") (name "CON_USB_P") (class "Default")
      (node (ref "D104") (pin "2") (pinfunction "2_2") (pintype "input"))
      (node (ref "J101") (pin "A6") (pinfunction "DP1_A6") (pintype "unspecified"))
      (node (ref "J101") (pin "B6") (pinfunction "DP2_B6") (pintype "unspecified"))
      (node (ref "R111") (pin "1") (pinfunction "1_1") (pintype "input"))
    )
    (net (code "12") (name "EXT_LEDS") (class "Default")
      (node (ref "J201") (pin "3") (pinfunction "3_3") (pintype "unspecified"))
      (node (ref "LED231") (pin "2") (pinfunction "DOUT_2") (pintype "unspecified"))
    )
    (net (code "13") (name "GND") (class "Default")
      (node (ref "C101") (pin "1") (pinfunction "1_1") (pintype "unspecified"))
      (node (ref "C102") (pin "1") (pinfunction "1_1") (pintype "unspecified"))
      (node (ref "C103") (pin "1") (pinfunction "1_1") (pintype "unspecified"))
      (node (ref "C104") (pin "1") (pinfunction "1_1") (pintype "unspecified"))
      (node (ref "C105") (pin "1") (pinfunction "1_1") (pintype "unspecified"))
      (node (ref "C106") (pin "1") (pinfunction "1_1") (pintype "unspecified"))
      (node (ref "C107") (pin "1") (pinfunction "1_1") (pintype "unspecified"))
      (node (ref "C108") (pin "1") (pinfunction "1_1") (pintype "unspecified"))
      (node (ref "C109") (pin "1") (pinfunction "1_1") (pintype "unspecified"))
      (node (ref "C110") (pin "1") (pinfunction "1_1") (pintype "unspecified"))
      (node (ref "C111") (pin "1") (pinfunction "1_1") (pintype "unspecified"))
      (node (ref "C112") (pin "1") (pinfunction "1_1") (pintype "unspecified"))
      (node (ref "C113") (pin "1") (pinfunction "1_1") (pintype "unspecified"))
      (node (ref "C114") (pin "1") (pinfunction "1_1") (pintype "unspecified"))
      (node (ref "C115") (pin "1") (pinfunction "1_1") (pintype "unspecified"))
      (node (ref "C116") (pin "1") (pinfunction "1_1") (pintype "unspecified"))
      (node (ref "C118") (pin "1") (pinfunction "1_1") (pintype "unspecified"))
      (node (ref "C119") (pin "1") (pinfunction "1_1") (pintype "unspecified"))
      (node (ref "C123") (pin "2") (pinfunction "2_2") (pintype "unspecified"))
      (node (ref "C124") (pin "2") (pinfunction "2_2") (pintype "unspecified"))
      (node (ref "C125") (pin "1") (pinfunction "1_1") (pintype "unspecified"))
      (node (ref "C126") (pin "1") (pinfunction "1_1") (pintype "unspecified"))
      (node (ref "C127") (pin "1") (pinfunction "1_1") (pintype "unspecified"))
      (node (ref "C210") (pin "1") (pinfunction "1_1") (pintype "unspecified"))
      (node (ref "C211") (pin "1") (pinfunction "1_1") (pintype "unspecified"))
      (node (ref "C212") (pin "1") (pinfunction "1_1") (pintype "unspecified"))
      (node (ref "C213") (pin "1") (pinfunction "1_1") (pintype "unspecified"))
      (node (ref "C214") (pin "1") (pinfunction "1_1") (pintype "unspecified"))
      (node (ref "C215") (pin "1") (pinfunction "1_1") (pintype "unspecified"))
      (node (ref "C216") (pin "1") (pinfunction "1_1") (pintype "unspecified"))
      (node (ref "C217") (pin "1") (pinfunction "1_1") (pintype "unspecified"))
      (node (ref "C218") (pin "1") (pinfunction "1_1") (pintype "unspecified"))
      (node (ref "C219") (pin "1") (pinfunction "1_1") (pintype "unspecified"))
      (node (ref "C220") (pin "1") (pinfunction "1_1") (pintype "unspecified"))
      (node (ref "C221") (pin "1") (pinfunction "1_1") (pintype "unspecified"))
      (node (ref "C222") (pin "1") (pinfunction "1_1") (pintype "unspecified"))
      (node (ref "C223") (pin "1") (pinfunction "1_1") (pintype "unspecified"))
      (node (ref "C224") (pin "1") (pinfunction "1_1") (pintype "unspecified"))
      (node (ref "C225") (pin "1") (pinfunction "1_1") (pintype "unspecified"))
      (node (ref "C226") (pin "1") (pinfunction "1_1") (pintype "unspecified"))
      (node (ref "C227") (pin "1") (pinfunction "1_1") (pintype "unspecified"))
      (node (ref "C228") (pin "1") (pinfunction "1_1") (pintype "unspecified"))
      (node (ref "C229") (pin "1") (pinfunction "1_1") (pintype "unspecified"))
      (node (ref "C230") (pin "1") (pinfunction "1_1") (pintype "unspecified"))
      (node (ref "C231") (pin "1") (pinfunction "1_1") (pintype "unspecified"))
      (node (ref "C232") (pin "1") (pinfunction "1_1") (pintype "unspecified"))
      (node (ref "C233") (pin "1") (pinfunction "1_1") (pintype "unspecified"))
      (node (ref "C234") (pin "1") (pinfunction "1_1") (pintype "unspecified"))
      (node (ref "C235") (pin "1") (pinfunction "1_1") (pintype "unspecified"))
      (node (ref "C236") (pin "1") (pinfunction "1_1") (pintype "unspecified"))
      (node (ref "C237") (pin "1") (pinfunction "1_1") (pintype "unspecified"))
      (node (ref "C238") (pin "1") (pinfunction "1_1") (pintype "unspecified"))
      (node (ref "C239") (pin "1") (pinfunction "1_1") (pintype "unspecified"))
      (node (ref "C240") (pin "1") (pinfunction "1_1") (pintype "unspecified"))
      (node (ref "C241") (pin "1") (pinfunction "1_1") (pintype "unspecified"))
      (node (ref "C242") (pin "1") (pinfunction "1_1") (pintype "unspecified"))
      (node (ref "C243") (pin "1") (pinfunction "1_1") (pintype "unspecified"))
      (node (ref "C244") (pin "1") (pinfunction "1_1") (pintype "unspecified"))
      (node (ref "C245") (pin "1") (pinfunction "1_1") (pintype "unspecified"))
      (node (ref "C246") (pin "1") (pinfunction "1_1") (pintype "unspecified"))
      (node (ref "C247") (pin "1") (pinfunction "1_1") (pintype "unspecified"))
      (node (ref "C248") (pin "1") (pinfunction "1_1") (pintype "unspecified"))
      (node (ref "D101") (pin "1") (pinfunction "1_1") (pintype "input"))
      (node (ref "D102") (pin "1") (pinfunction "1_1") (pintype "input"))
      (node (ref "D103") (pin "1") (pinfunction "1_1") (pintype "input"))
      (node (ref "D104") (pin "1") (pinfunction "1_1") (pintype "input"))
      (node (ref "J101") (pin "13") (pinfunction "SH_13") (pintype "unspecified"))
      (node (ref "J101") (pin "A12B1") (pinfunction "GND_A12B1") (pintype "unspecified"))
      (node (ref "J101") (pin "A1B12") (pinfunction "GND_A1B12") (pintype "unspecified"))
      (node (ref "J201") (pin "2") (pinfunction "2_2") (pintype "unspecified"))
      (node (ref "LED102") (pin "2") (pinfunction "K_2") (pintype "unspecified"))
      (node (ref "LED201") (pin "3") (pinfunction "GND_3") (pintype "unspecified"))
      (node (ref "LED202") (pin "3") (pinfunction "GND_3") (pintype "unspecified"))
      (node (ref "LED203") (pin "3") (pinfunction "GND_3") (pintype "unspecified"))
      (node (ref "LED204") (pin "3") (pinfunction "GND_3") (pintype "unspecified"))
      (node (ref "LED205") (pin "3") (pinfunction "GND_3") (pintype "unspecified"))
      (node (ref "LED206") (pin "3") (pinfunction "GND_3") (pintype "unspecified"))
      (node (ref "LED207") (pin "3") (pinfunction "GND_3") (pintype "unspecified"))
      (node (ref "LED208") (pin "3") (pinfunction "GND_3") (pintype "unspecified"))
      (node (ref "LED209") (pin "3") (pinfunction "GND_3") (pintype "unspecified"))
      (node (ref "LED210") (pin "3") (pinfunction "GND_3") (pintype "unspecified"))
      (node (ref "LED211") (pin "3") (pinfunction "GND_3") (pintype "unspecified"))
      (node (ref "LED212") (pin "3") (pinfunction "GND_3") (pintype "unspecified"))
      (node (ref "LED213") (pin "3") (pinfunction "GND_3") (pintype "unspecified"))
      (node (ref "LED214") (pin "3") (pinfunction "GND_3") (pintype "unspecified"))
      (node (ref "LED215") (pin "3") (pinfunction "GND_3") (pintype "unspecified"))
      (node (ref "LED216") (pin "3") (pinfunction "GND_3") (pintype "unspecified"))
      (node (ref "LED217") (pin "3") (pinfunction "GND_3") (pintype "unspecified"))
      (node (ref "LED218") (pin "3") (pinfunction "GND_3") (pintype "unspecified"))
      (node (ref "LED219") (pin "3") (pinfunction "GND_3") (pintype "unspecified"))
      (node (ref "LED220") (pin "3") (pinfunction "GND_3") (pintype "unspecified"))
      (node (ref "LED221") (pin "3") (pinfunction "GND_3") (pintype "unspecified"))
      (node (ref "LED222") (pin "3") (pinfunction "GND_3") (pintype "unspecified"))
      (node (ref "LED223") (pin "3") (pinfunction "GND_3") (pintype "unspecified"))
      (node (ref "LED224") (pin "3") (pinfunction "GND_3") (pintype "unspecified"))
      (node (ref "LED225") (pin "3") (pinfunction "GND_3") (pintype "unspecified"))
      (node (ref "LED226") (pin "3") (pinfunction "GND_3") (pintype "unspecified"))
      (node (ref "LED227") (pin "3") (pinfunction "GND_3") (pintype "unspecified"))
      (node (ref "LED228") (pin "3") (pinfunction "GND_3") (pintype "unspecified"))
      (node (ref "LED229") (pin "3") (pinfunction "GND_3") (pintype "unspecified"))
      (node (ref "LED230") (pin "3") (pinfunction "GND_3") (pintype "unspecified"))
      (node (ref "LED231") (pin "3") (pinfunction "GND_3") (pintype "unspecified"))
      (node (ref "MH205") (pin "1") (pinfunction "1_1") (pintype "input"))
      (node (ref "MH206") (pin "1") (pinfunction "1_1") (pintype "input"))
      (node (ref "MH207") (pin "1") (pinfunction "1_1") (pintype "input"))
      (node (ref "MH208") (pin "1") (pinfunction "1_1") (pintype "input"))
      (node (ref "Q1") (pin "2") (pinfunction "S_2") (pintype "unspecified"))
      (node (ref "R118") (pin "1") (pinfunction "1_1") (pintype "input"))
      (node (ref "R119") (pin "1") (pinfunction "1_1") (pintype "input"))
      (node (ref "R128") (pin "1") (pinfunction "1_1") (pintype "input"))
      (node (ref "R135") (pin "2") (pinfunction "2_2") (pintype "input"))
      (node (ref "SW101") (pin "1") (pinfunction "A_1") (pintype "input"))
      (node (ref "SW101") (pin "2") (pinfunction "B_2") (pintype "input"))
      (node (ref "SW102") (pin "1") (pinfunction "A_1") (pintype "input"))
      (node (ref "SW102") (pin "2") (pinfunction "B_2") (pintype "input"))
      (node (ref "SW103") (pin "1") (pinfunction "1_1") (pintype "input"))
      (node (ref "SW103") (pin "2") (pinfunction "2_2") (pintype "input"))
      (node (ref "SW104") (pin "1") (pinfunction "1_1") (pintype "input"))
      (node (ref "SW104") (pin "2") (pinfunction "2_2") (pintype "input"))
      (node (ref "SW105") (pin "1") (pinfunction "1_1") (pintype "input"))
      (node (ref "SW105") (pin "2") (pinfunction "2_2") (pintype "input"))
      (node (ref "U101") (pin "19") (pinfunction "TESTEN_19") (pintype "unspecified"))
      (node (ref "U101") (pin "57") (pinfunction "GND_57") (pintype "bidirectional"))
      (node (ref "U102") (pin "2") (pinfunction "GND_2") (pintype "unspecified"))
      (node (ref "U102") (pin "4") (pinfunction "GND_4") (pintype "unspecified"))
      (node (ref "U103") (pin "3") (pinfunction "GND_3") (pintype "unspecified"))
      (node (ref "U104") (pin "4") (pinfunction "GND_4") (pintype "unspecified"))
      (node (ref "U105") (pin "3") (pinfunction "GND_3") (pintype "unspecified"))
      (node (ref "U106") (pin "5") (pinfunction "GND_5") (pintype "unspecified"))
      (node (ref "U106") (pin "9") (pinfunction "EP_9") (pintype "unspecified"))
      (node (ref "U107") (pin "3") (pinfunction "3_3") (pintype "input"))
      (node (ref "Y101") (pin "2") (pinfunction "GND_2") (pintype "input"))
      (node (ref "Y101") (pin "4") (pinfunction "GND_4") (pintype "input"))
    )
    (net (code "14") (name "I2C1_SCL") (class "Default")
      (node (ref "R137") (pin "1") (pinfunction "1_1") (pintype "input"))
      (node (ref "U101") (pin "14") (pinfunction "GPIO11_14") (pintype "bidirectional"))
      (node (ref "U106") (pin "8") (pinfunction "SCL_8") (pintype "unspecified"))
    )
    (net (code "15") (name "I2C1_SDA") (class "Default")
      (node (ref "R138") (pin "1") (pinfunction "1_1") (pintype "input"))
      (node (ref "U101") (pin "13") (pinfunction "GPIO10_13") (pintype "bidirectional"))
      (node (ref "U106") (pin "7") (pinfunction "SDA_7") (pintype "unspecified"))
    )
    (net (code "16") (name "LED0_BUF") (class "Default")
      (node (ref "U101") (pin "29") (pinfunction "GPIO18_29") (pintype "bidirectional"))
      (node (ref "U103") (pin "1") (pinfunction "NC_1") (pintype "unspecified"))
      (node (ref "U103") (pin "2") (pinfunction "A_2") (pintype "unspecified"))
    )
    (net (code "17") (name "LED0_DIN") (class "Default")
      (node (ref "LED201") (pin "4") (pinfunction "DIN_4") (pintype "unspecified"))
      (node (ref "U103") (pin "4") (pinfunction "Y_4") (pintype "unspecified"))
    )
    (net (code "18") (name "LED1_DIN") (class "Default")
      (node (ref "LED201") (pin "2") (pinfunction "DOUT_2") (pintype "unspecified"))
      (node (ref "LED202") (pin "4") (pinfunction "DIN_4") (pintype "unspecified"))
    )
    (net (code "19") (name "LED2_DIN") (class "Default")
      (node (ref "LED202") (pin "2") (pinfunction "DOUT_2") (pintype "unspecified"))
      (node (ref "LED203") (pin "4") (pinfunction "DIN_4") (pintype "unspecified"))
    )
    (net (code "20") (name "LED3_DIN") (class "Default")
      (node (ref "LED203") (pin "2") (pinfunction "DOUT_2") (pintype "unspecified"))
      (node (ref "LED204") (pin "4") (pinfunction "DIN_4") (pintype "unspecified"))
    )
    (net (code "21") (name "LED4_DIN") (class "Default")
      (node (ref "LED204") (pin "2") (pinfunction "DOUT_2") (pintype "unspecified"))
      (node (ref "LED205") (pin "4") (pinfunction "DIN_4") (pintype "unspecified"))
    )
    (net (code "22") (name "LED5_DIN") (class "Default")
      (node (ref "LED205") (pin "2") (pinfunction "DOUT_2") (pintype "unspecified"))
      (node (ref "LED206") (pin "4") (pinfunction "DIN_4") (pintype "unspecified"))
    )
    (net (code "23") (name "LED6_DIN") (class "Default")
      (node (ref "LED206") (pin "2") (pinfunction "DOUT_2") (pintype "unspecified"))
      (node (ref "LED207") (pin "4") (pinfunction "DIN_4") (pintype "unspecified"))
    )
    (net (code "24") (name "LED7_DIN") (class "Default")
      (node (ref "LED207") (pin "2") (pinfunction "DOUT_2") (pintype "unspecified"))
      (node (ref "LED208") (pin "4") (pinfunction "DIN_4") (pintype "unspecified"))
    )
    (net (code "25") (name "LED8_DIN") (class "Default")
      (node (ref "LED208") (pin "2") (pinfunction "DOUT_2") (pintype "unspecified"))
      (node (ref "LED209") (pin "4") (pinfunction "DIN_4") (pintype "unspecified"))
    )
    (net (code "26") (name "LED9_DIN") (class "Default")
      (node (ref "LED209") (pin "2") (pinfunction "DOUT_2") (pintype "unspecified"))
      (node (ref "LED210") (pin "4") (pinfunction "DIN_4") (pintype "unspecified"))
    )
    (net (code "27") (name "LED10_DIN") (class "Default")
      (node (ref "LED210") (pin "2") (pinfunction "DOUT_2") (pintype "unspecified"))
      (node (ref "LED211") (pin "4") (pinfunction "DIN_4") (pintype "unspecified"))
    )
    (net (code "28") (name "LED11_DIN") (class "Default")
      (node (ref "LED211") (pin "2") (pinfunction "DOUT_2") (pintype "unspecified"))
      (node (ref "LED212") (pin "4") (pinfunction "DIN_4") (pintype "unspecified"))
    )
    (net (code "29") (name "LED12_DIN") (class "Default")
      (node (ref "LED212") (pin "2") (pinfunction "DOUT_2") (pintype "unspecified"))
      (node (ref "LED213") (pin "4") (pinfunction "DIN_4") (pintype "unspecified"))
    )
    (net (code "30") (name "LED13_DIN") (class "Default")
      (node (ref "LED213") (pin "2") (pinfunction "DOUT_2") (pintype "unspecified"))
      (node (ref "LED214") (pin "4") (pinfunction "DIN_4") (pintype "unspecified"))
    )
    (net (code "31") (name "LED14_DIN") (class "Default")
      (node (ref "LED214") (pin "2") (pinfunction "DOUT_2") (pintype "unspecified"))
      (node (ref "LED215") (pin "4") (pinfunction "DIN_4") (pintype "unspecified"))
    )
    (net (code "32") (name "LED15_DIN") (class "Default")
      (node (ref "LED215") (pin "2") (pinfunction "DOUT_2") (pintype "unspecified"))
      (node (ref "LED216") (pin "4") (pinfunction "DIN_4") (pintype "unspecified"))
    )
    (net (code "33") (name "LED16_DIN") (class "Default")
      (node (ref "LED216") (pin "2") (pinfunction "DOUT_2") (pintype "unspecified"))
      (node (ref "LED217") (pin "4") (pinfunction "DIN_4") (pintype "unspecified"))
    )
    (net (code "34") (name "LED17_DIN") (class "Default")
      (node (ref "LED217") (pin "2") (pinfunction "DOUT_2") (pintype "unspecified"))
      (node (ref "LED218") (pin "4") (pinfunction "DIN_4") (pintype "unspecified"))
    )
    (net (code "35") (name "LED18_DIN") (class "Default")
      (node (ref "LED218") (pin "2") (pinfunction "DOUT_2") (pintype "unspecified"))
      (node (ref "LED219") (pin "4") (pinfunction "DIN_4") (pintype "unspecified"))
    )
    (net (code "36") (name "LED19_DIN") (class "Default")
      (node (ref "LED219") (pin "2") (pinfunction "DOUT_2") (pintype "unspecified"))
      (node (ref "LED220") (pin "4") (pinfunction "DIN_4") (pintype "unspecified"))
    )
    (net (code "37") (name "LED20_DIN") (class "Default")
      (node (ref "LED220") (pin "2") (pinfunction "DOUT_2") (pintype "unspecified"))
      (node (ref "LED221") (pin "4") (pinfunction "DIN_4") (pintype "unspecified"))
    )
    (net (code "38") (name "LED21_DIN") (class "Default")
      (node (ref "LED221") (pin "2") (pinfunction "DOUT_2") (pintype "unspecified"))
      (node (ref "LED222") (pin "4") (pinfunction "DIN_4") (pintype "unspecified"))
    )
    (net (code "39") (name "LED22_DIN") (class "Default")
      (node (ref "LED222") (pin "2") (pinfunction "DOUT_2") (pintype "unspecified"))
      (node (ref "LED223") (pin "4") (pinfunction "DIN_4") (pintype "unspecified"))
    )
    (net (code "40") (name "LED23_DIN") (class "Default")
      (node (ref "LED223") (pin "2") (pinfunction "DOUT_2") (pintype "unspecified"))
      (node (ref "LED224") (pin "4") (pinfunction "DIN_4") (pintype "unspecified"))
    )
    (net (code "41") (name "LED24_DIN") (class "Default")
      (node (ref "LED224") (pin "2") (pinfunction "DOUT_2") (pintype "unspecified"))
      (node (ref "LED225") (pin "4") (pinfunction "DIN_4") (pintype "unspecified"))
    )
    (net (code "42") (name "LED25_DIN") (class "Default")
      (node (ref "LED225") (pin "2") (pinfunction "DOUT_2") (pintype "unspecified"))
      (node (ref "LED226") (pin "4") (pinfunction "DIN_4") (pintype "unspecified"))
    )
    (net (code "43") (name "LED26_DIN") (class "Default")
      (node (ref "LED226") (pin "2") (pinfunction "DOUT_2") (pintype "unspecified"))
      (node (ref "LED227") (pin "4") (pinfunction "DIN_4") (pintype "unspecified"))
    )
    (net (code "44") (name "LED27_DIN") (class "Default")
      (node (ref "LED227") (pin "2") (pinfunction "DOUT_2") (pintype "unspecified"))
      (node (ref "LED228") (pin "4") (pinfunction "DIN_4") (pintype "unspecified"))
    )
    (net (code "45") (name "LED28_BUF") (class "Default")
      (node (ref "U101") (pin "40") (pinfunction "GPIO28_ADC2_40") (pintype "bidirectional"))
      (node (ref "U105") (pin "1") (pinfunction "NC_1") (pintype "unspecified"))
      (node (ref "U105") (pin "2") (pinfunction "A_2") (pintype "unspecified"))
    )
    (net (code "46") (name "LED28_DIN") (class "Default")
      (node (ref "LED229") (pin "4") (pinfunction "DIN_4") (pintype "unspecified"))
      (node (ref "U105") (pin "4") (pinfunction "Y_4") (pintype "unspecified"))
    )
    (net (code "47") (name "LED29_DIN") (class "Default")
      (node (ref "LED229") (pin "2") (pinfunction "DOUT_2") (pintype "unspecified"))
      (node (ref "LED230") (pin "4") (pinfunction "DIN_4") (pintype "unspecified"))
    )
    (net (code "48") (name "LED30_DIN") (class "Default")
      (node (ref "LED230") (pin "2") (pinfunction "DOUT_2") (pintype "unspecified"))
      (node (ref "LED231") (pin "4") (pinfunction "DIN_4") (pintype "unspecified"))
    )
    (net (code "49") (name "LIGHT_DET") (class "Default")
      (node (ref "C247") (pin "2") (pinfunction "2_2") (pintype "unspecified"))
      (node (ref "R135") (pin "1") (pinfunction "1_1") (pintype "input"))
      (node (ref "R136") (pin "1") (pinfunction "1_1") (pintype "input"))
      (node (ref "U101") (pin "39") (pinfunction "GPIO27_ADC1_39") (pintype "bidirectional"))
    )
    (net (code "50") (name "Net-(D105-A)") (class "Default")
      (node (ref "BUZZER1") (pin "2") (pinfunction "2_2") (pintype "unspecified"))
      (node (ref "D105") (pin "2") (pinfunction "A_2") (pintype "unspecified"))
      (node (ref "Q1") (pin "3") (pinfunction "D_3") (pintype "unspecified"))
    )
    (net (code "51") (name "Net-(D105-K)") (class "Default")
      (node (ref "BUZZER1") (pin "1") (pinfunction "1_1") (pintype "unspecified"))
      (node (ref "C243") (pin "2") (pinfunction "2_2") (pintype "unspecified"))
      (node (ref "D105") (pin "1") (pinfunction "K_1") (pintype "unspecified"))
      (node (ref "R127") (pin "1") (pinfunction "1_1") (pintype "unspecified"))
    )
    (net (code "52") (name "Net-(J101-CC1)") (class "Default")
      (node (ref "J101") (pin "A5") (pinfunction "CC1_A5") (pintype "unspecified"))
      (node (ref "R119") (pin "2") (pinfunction "2_2") (pintype "input"))
    )
    (net (code "53") (name "Net-(J101-CC2)") (class "Default")
      (node (ref "J101") (pin "B5") (pinfunction "CC2_B5") (pintype "unspecified"))
      (node (ref "R118") (pin "2") (pinfunction "2_2") (pintype "input"))
    )
    (net (code "54") (name "Net-(LED102-A)") (class "Default")
      (node (ref "LED102") (pin "1") (pinfunction "A_1") (pintype "unspecified"))
      (node (ref "R104") (pin "1") (pinfunction "1_1") (pintype "input"))
    )
    (net (code "55") (name "Net-(R129-Pad1)") (class "Default")
      (node (ref "R129") (pin "1") (pinfunction "1_1") (pintype "input"))
      (node (ref "R130") (pin "1") (pinfunction "1_1") (pintype "input"))
      (node (ref "SW103") (pin "3") (pinfunction "3_3") (pintype "input"))
      (node (ref "SW103") (pin "4") (pinfunction "4_4") (pintype "input"))
    )
    (net (code "56") (name "Net-(R131-Pad1)") (class "Default")
      (node (ref "R131") (pin "1") (pinfunction "1_1") (pintype "input"))
      (node (ref "R132") (pin "1") (pinfunction "1_1") (pintype "input"))
      (node (ref "SW104") (pin "3") (pinfunction "3_3") (pintype "input"))
      (node (ref "SW104") (pin "4") (pinfunction "4_4") (pintype "input"))
    )
    (net (code "57") (name "Net-(R133-Pad1)") (class "Default")
      (node (ref "R133") (pin "1") (pinfunction "1_1") (pintype "input"))
      (node (ref "R134") (pin "1") (pinfunction "1_1") (pintype "input"))
      (node (ref "SW105") (pin "3") (pinfunction "3_3") (pintype "input"))
      (node (ref "SW105") (pin "4") (pinfunction "4_4") (pintype "input"))
    )
    (net (code "58") (name "Net-(SW101-C)") (class "Default")
      (node (ref "R122") (pin "1") (pinfunction "1_1") (pintype "input"))
      (node (ref "R124") (pin "1") (pinfunction "1_1") (pintype "input"))
      (node (ref "SW101") (pin "3") (pinfunction "C_3") (pintype "input"))
      (node (ref "SW101") (pin "4") (pinfunction "D_4") (pintype "input"))
    )
    (net (code "59") (name "Net-(SW102-C)") (class "Default")
      (node (ref "R123") (pin "1") (pinfunction "1_1") (pintype "input"))
      (node (ref "R125") (pin "1") (pinfunction "1_1") (pintype "input"))
      (node (ref "SW102") (pin "3") (pinfunction "C_3") (pintype "input"))
      (node (ref "SW102") (pin "4") (pinfunction "D_4") (pintype "input"))
    )
    (net (code "60") (name "QSPI_SCLK") (class "Default")
      (node (ref "U101") (pin "52") (pinfunction "QSPI_SCLK_52") (pintype "output"))
      (node (ref "U104") (pin "6") (pinfunction "CLK_6") (pintype "unspecified"))
    )
    (net (code "61") (name "QSPI_SD0") (class "Default")
      (node (ref "U101") (pin "53") (pinfunction "QSPI_SD0_53") (pintype "bidirectional"))
      (node (ref "U104") (pin "5") (pinfunction "DI_5") (pintype "unspecified"))
    )
    (net (code "62") (name "QSPI_SD1") (class "Default")
      (node (ref "U101") (pin "55") (pinfunction "QSPI_SD1_55") (pintype "bidirectional"))
      (node (ref "U104") (pin "2") (pinfunction "DO_2") (pintype "unspecified"))
    )
    (net (code "63") (name "QSPI_SD2") (class "Default")
      (node (ref "U101") (pin "54") (pinfunction "QSPI_SD2_54") (pintype "bidirectional"))
      (node (ref "U104") (pin "3") (pinfunction "IO2_3") (pintype "unspecified"))
    )
    (net (code "64") (name "QSPI_SD3") (class "Default")
      (node (ref "U101") (pin "51") (pinfunction "QSPI_SD3_51") (pintype "bidirectional"))
      (node (ref "U104") (pin "7") (pinfunction "IO3_7") (pintype "unspecified"))
    )
    (net (code "65") (name "QSPI_SS") (class "Default")
      (node (ref "R124") (pin "2") (pinfunction "2_2") (pintype "input"))
      (node (ref "U101") (pin "56") (pinfunction "QSPI_SS_56") (pintype "bidirectional"))
      (node (ref "U104") (pin "1") (pinfunction "CS#_1") (pintype "unspecified"))
    )
    (net (code "66") (name "RESET_N") (class "Default")
      (node (ref "C127") (pin "2") (pinfunction "2_2") (pintype "unspecified"))
      (node (ref "R125") (pin "2") (pinfunction "2_2") (pintype "input"))
      (node (ref "U101") (pin "26") (pinfunction "RUN_26") (pintype "input"))
    )
    (net (code "67") (name "USB_N") (class "Default")
      (node (ref "R109") (pin "2") (pinfunction "2_2") (pintype "input"))
      (node (ref "U101") (pin "46") (pinfunction "USB_DM_46") (pintype "bidirectional"))
    )
    (net (code "68") (name "USB_P") (class "Default")
      (node (ref "R111") (pin "2") (pinfunction "2_2") (pintype "input"))
      (node (ref "U101") (pin "47") (pinfunction "USB_DP_47") (pintype "bidirectional"))
    )
    (net (code "69") (name "USER_BTN1") (class "Default")
      (node (ref "C244") (pin "2") (pinfunction "2_2") (pintype "unspecified"))
      (node (ref "R130") (pin "2") (pinfunction "2_2") (pintype "input"))
      (node (ref "U101") (pin "18") (pinfunction "GPIO15_18") (pintype "bidirectional"))
    )
    (net (code "70") (name "USER_BTN2") (class "Default")
      (node (ref "C245") (pin "2") (pinfunction "2_2") (pintype "unspecified"))
      (node (ref "R132") (pin "2") (pinfunction "2_2") (pintype "input"))
      (node (ref "U101") (pin "17") (pinfunction "GPIO14_17") (pintype "bidirectional"))
    )
    (net (code "71") (name "USER_BTN3") (class "Default")
      (node (ref "C246") (pin "2") (pinfunction "2_2") (pintype "unspecified"))
      (node (ref "R134") (pin "2") (pinfunction "2_2") (pintype "input"))
      (node (ref "U101") (pin "16") (pinfunction "GPIO13_16") (pintype "bidirectional"))
    )
    (net (code "72") (name "XIN") (class "Default")
      (node (ref "C123") (pin "1") (pinfunction "1_1") (pintype "unspecified"))
      (node (ref "R120") (pin "2") (pinfunction "2_2") (pintype "input"))
      (node (ref "U101") (pin "20") (pinfunction "XIN_20") (pintype "input"))
      (node (ref "Y101") (pin "1") (pinfunction "1_1") (pintype "input"))
    )
    (net (code "73") (name "XOUT") (class "Default")
      (node (ref "R120") (pin "1") (pinfunction "1_1") (pintype "input"))
      (node (ref "R121") (pin "2") (pinfunction "2_2") (pintype "input"))
      (node (ref "U101") (pin "21") (pinfunction "XOUT_21") (pintype "unspecified"))
    )
    (net (code "74") (name "X_R") (class "Default")
      (node (ref "C124") (pin "1") (pinfunction "1_1") (pintype "unspecified"))
      (node (ref "R121") (pin "1") (pinfunction "1_1") (pintype "input"))
      (node (ref "Y101") (pin "3") (pinfunction "3_3") (pintype "input"))
    )
    (net (code "75") (name "unconnected-(J101-SBU1-PadA8)") (class "Default")
      (node (ref "J101") (pin "A8") (pinfunction "SBU1_A8") (pintype "unspecified+no_connect"))
    )
    (net (code "76") (name "unconnected-(J101-SBU2-PadB8)") (class "Default")
      (node (ref "J101") (pin "B8") (pinfunction "SBU2_B8") (pintype "unspecified+no_connect"))
    )
    (net (code "77") (name "unconnected-(LED228-DOUT-Pad2)") (class "Default")
      (node (ref "LED228") (pin "2") (pinfunction "DOUT_2") (pintype "unspecified+no_connect"))
    )
    (net (code "78") (name "unconnected-(U101-GPIO0-Pad2)") (class "Default")
      (node (ref "U101") (pin "2") (pinfunction "GPIO0_2") (pintype "bidirectional+no_connect"))
    )
    (net (code "79") (name "unconnected-(U101-GPIO1-Pad3)") (class "Default")
      (node (ref "U101") (pin "3") (pinfunction "GPIO1_3") (pintype "bidirectional+no_connect"))
    )
    (net (code "80") (name "unconnected-(U101-GPIO2-Pad4)") (class "Default")
      (node (ref "U101") (pin "4") (pinfunction "GPIO2_4") (pintype "bidirectional+no_connect"))
    )
    (net (code "81") (name "unconnected-(U101-GPIO3-Pad5)") (class "Default")
      (node (ref "U101") (pin "5") (pinfunction "GPIO3_5") (pintype "bidirectional+no_connect"))
    )
    (net (code "82") (name "unconnected-(U101-GPIO4-Pad6)") (class "Default")
      (node (ref "U101") (pin "6") (pinfunction "GPIO4_6") (pintype "bidirectional+no_connect"))
    )
    (net (code "83") (name "unconnected-(U101-GPIO5-Pad7)") (class "Default")
      (node (ref "U101") (pin "7") (pinfunction "GPIO5_7") (pintype "bidirectional+no_connect"))
    )
    (net (code "84") (name "unconnected-(U101-GPIO6-Pad8)") (class "Default")
      (node (ref "U101") (pin "8") (pinfunction "GPIO6_8") (pintype "bidirectional+no_connect"))
    )
    (net (code "85") (name "unconnected-(U101-GPIO7-Pad9)") (class "Default")
      (node (ref "U101") (pin "9") (pinfunction "GPIO7_9") (pintype "bidirectional+no_connect"))
    )
    (net (code "86") (name "unconnected-(U101-GPIO8-Pad11)") (class "Default")
      (node (ref "U101") (pin "11") (pinfunction "GPIO8_11") (pintype "bidirectional+no_connect"))
    )
    (net (code "87") (name "unconnected-(U101-GPIO12-Pad15)") (class "Default")
      (node (ref "U101") (pin "15") (pinfunction "GPIO12_15") (pintype "bidirectional+no_connect"))
    )
    (net (code "88") (name "unconnected-(U101-GPIO16-Pad27)") (class "Default")
      (node (ref "U101") (pin "27") (pinfunction "GPIO16_27") (pintype "bidirectional+no_connect"))
    )
    (net (code "89") (name "unconnected-(U101-GPIO17-Pad28)") (class "Default")
      (node (ref "U101") (pin "28") (pinfunction "GPIO17_28") (pintype "bidirectional+no_connect"))
    )
    (net (code "90") (name "unconnected-(U101-GPIO19-Pad30)") (class "Default")
      (node (ref "U101") (pin "30") (pinfunction "GPIO19_30") (pintype "bidirectional+no_connect"))
    )
    (net (code "91") (name "unconnected-(U101-GPIO20-Pad31)") (class "Default")
      (node (ref "U101") (pin "31") (pinfunction "GPIO20_31") (pintype "bidirectional+no_connect"))
    )
    (net (code "92") (name "unconnected-(U101-GPIO21-Pad32)") (class "Default")
      (node (ref "U101") (pin "32") (pinfunction "GPIO21_32") (pintype "bidirectional+no_connect"))
    )
    (net (code "93") (name "unconnected-(U101-GPIO22-Pad34)") (class "Default")
      (node (ref "U101") (pin "34") (pinfunction "GPIO22_34") (pintype "bidirectional+no_connect"))
    )
    (net (code "94") (name "unconnected-(U101-GPIO23-Pad35)") (class "Default")
      (node (ref "U101") (pin "35") (pinfunction "GPIO23_35") (pintype "bidirectional+no_connect"))
    )
    (net (code "95") (name "unconnected-(U101-GPIO24-Pad36)") (class "Default")
      (node (ref "U101") (pin "36") (pinfunction "GPIO24_36") (pintype "bidirectional+no_connect"))
    )
    (net (code "96") (name "unconnected-(U101-GPIO25-Pad37)") (class "Default")
      (node (ref "U101") (pin "37") (pinfunction "GPIO25_37") (pintype "bidirectional+no_connect"))
    )
    (net (code "97") (name "unconnected-(U101-GPIO26_ADC0-Pad38)") (class "Default")
      (node (ref "U101") (pin "38") (pinfunction "GPIO26_ADC0_38") (pintype "bidirectional+no_connect"))
    )
    (net (code "98") (name "unconnected-(U101-SWCLK-Pad24)") (class "Default")
      (node (ref "U101") (pin "24") (pinfunction "SWCLK_24") (pintype "output+no_connect"))
    )
    (net (code "99") (name "unconnected-(U101-SWD-Pad25)") (class "Default")
      (node (ref "U101") (pin "25") (pinfunction "SWD_25") (pintype "bidirectional+no_connect"))
    )
    (net (code "100") (name "unconnected-(U106-CLKO-Pad1)") (class "Default")
      (node (ref "U106") (pin "1") (pinfunction "CLKO_1") (pintype "unspecified+no_connect"))
    )
    (net (code "101") (name "unconnected-(U106-INT#-Pad3)") (class "Default")
      (node (ref "U106") (pin "3") (pinfunction "INT#_3") (pintype "unspecified+no_connect"))
    )
  )
)
